# SI5324_CDR_DCXO_oscillators.net
KiCad netlist of a schematic drawn in Altium Designer
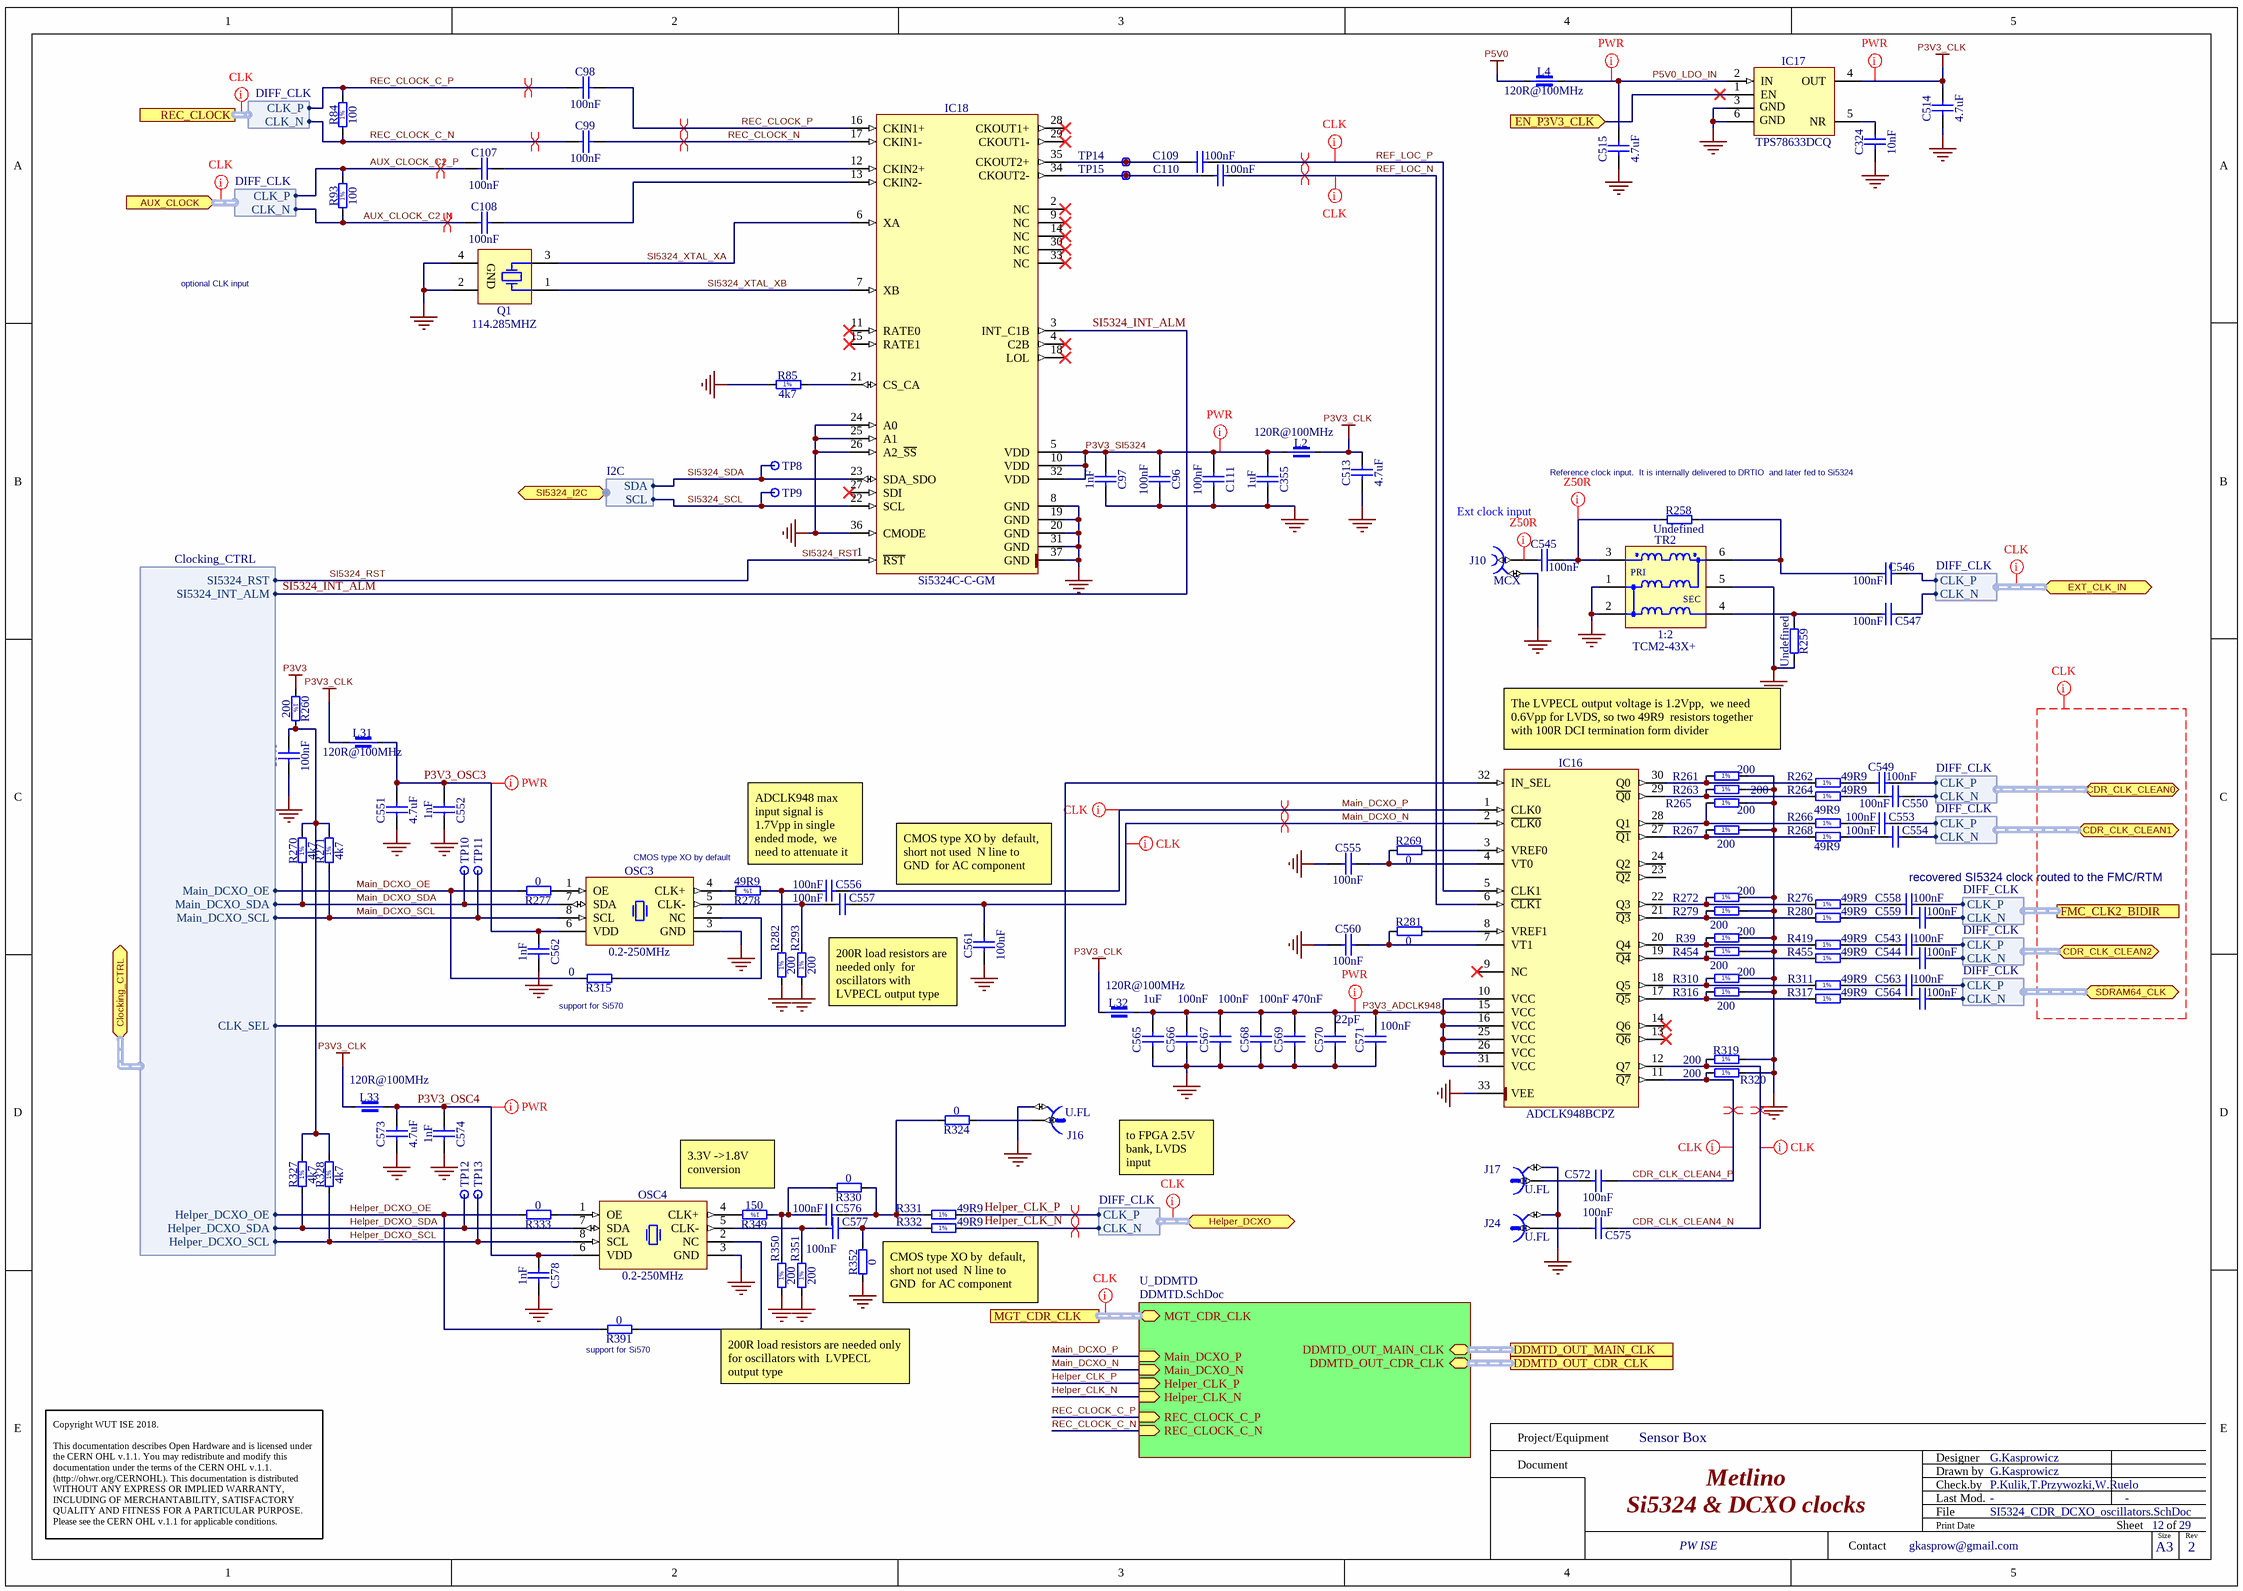
[diagram p0: SI5324_CDR_DCXO_oscillators.SchDoc]

(export (version "E")
  (design (tool "Eeschema 10.0.6"))
  (components
    (comp (ref "C96")
      (value "100nF")
      (footprint "CAPC0603X33N")
      (description "Non-polarised capacitor")
      (fields
        (field (name "MANUFACTURER PART NUMBER") "CC0201_100NF_6.3V_10%_X5R")
        (field (name "MANUFACTURER") "GENERIC")
        (field (name "AUTHOR") "CERN DEM JLC")
      )
      (libsource (lib "Capacitors") (part "Capacitor - non polarized"))
    )
    (comp (ref "C97")
      (value "1nF")
      (footprint "CAPC0603X33N")
      (description "Non-polarised capacitor")
      (fields
        (field (name "MANUFACTURER PART NUMBER") "CC0201_1NF_16V_10%_X5R")
        (field (name "MANUFACTURER") "GENERIC")
        (field (name "AUTHOR") "CERN DEM JLC")
      )
      (libsource (lib "Capacitors") (part "Capacitor - non polarized"))
    )
    (comp (ref "C98")
      (value "100nF")
      (footprint "CAPC0603X33N")
      (description "Non-polarised capacitor")
      (fields
        (field (name "MANUFACTURER PART NUMBER") "CC0201_100NF_6.3V_10%_X5R")
        (field (name "MANUFACTURER") "GENERIC")
        (field (name "AUTHOR") "CERN DEM JLC")
      )
      (libsource (lib "Capacitors") (part "Capacitor - non polarized"))
    )
    (comp (ref "C99")
      (value "100nF")
      (footprint "CAPC0603X33N")
      (description "Non-polarised capacitor")
      (fields
        (field (name "MANUFACTURER PART NUMBER") "CC0201_100NF_6.3V_10%_X5R")
        (field (name "MANUFACTURER") "GENERIC")
        (field (name "AUTHOR") "CERN DEM JLC")
      )
      (libsource (lib "Capacitors") (part "Capacitor - non polarized"))
    )
    (comp (ref "C107")
      (value "100nF")
      (footprint "CAPC0603X33N")
      (description "Non-polarised capacitor")
      (fields
        (field (name "MANUFACTURER PART NUMBER") "CC0201_100NF_6.3V_10%_X5R")
        (field (name "MANUFACTURER") "GENERIC")
        (field (name "AUTHOR") "CERN DEM JLC")
      )
      (libsource (lib "Capacitors") (part "Capacitor - non polarized"))
    )
    (comp (ref "C108")
      (value "100nF")
      (footprint "CAPC0603X33N")
      (description "Non-polarised capacitor")
      (fields
        (field (name "MANUFACTURER PART NUMBER") "CC0201_100NF_6.3V_10%_X5R")
        (field (name "MANUFACTURER") "GENERIC")
        (field (name "AUTHOR") "CERN DEM JLC")
      )
      (libsource (lib "Capacitors") (part "Capacitor - non polarized"))
    )
    (comp (ref "C109")
      (value "100nF")
      (footprint "CAPC1005X55N")
      (description "Non-polarised capacitor")
      (fields
        (field (name "MANUFACTURER PART NUMBER") "CC0402_100NF_16V_10%_X5R")
        (field (name "MANUFACTURER") "GENERIC")
        (field (name "AUTHOR") "CERN DEM JLC")
      )
      (libsource (lib "Capacitors") (part "Capacitor - non polarized"))
    )
    (comp (ref "C110")
      (value "100nF")
      (footprint "CAPC1005X55N")
      (description "Non-polarised capacitor")
      (fields
        (field (name "MANUFACTURER PART NUMBER") "CC0402_100NF_16V_10%_X5R")
        (field (name "MANUFACTURER") "GENERIC")
        (field (name "AUTHOR") "CERN DEM JLC")
      )
      (libsource (lib "Capacitors") (part "Capacitor - non polarized"))
    )
    (comp (ref "C111")
      (value "100nF")
      (footprint "CAPC0603X33N")
      (description "Non-polarised capacitor")
      (fields
        (field (name "MANUFACTURER PART NUMBER") "CC0201_100NF_6.3V_10%_X5R")
        (field (name "MANUFACTURER") "GENERIC")
        (field (name "AUTHOR") "CERN DEM JLC")
      )
      (libsource (lib "Capacitors") (part "Capacitor - non polarized"))
    )
    (comp (ref "C324")
      (value "10nF")
      (footprint "CAPC1608X87N")
      (description "Non-polarised capacitor")
      (fields
        (field (name "PART NUMBER") "CC0603_10NF_50V_5%_C0G")
        (field (name "VOLTAGE") "50V")
        (field (name "AUTHOR") "CERN DEM JLC")
      )
      (libsource (lib "Capacitors") (part "Capacitor - non polarized"))
    )
    (comp (ref "C355")
      (value "1uF")
      (footprint "CAPC1005X55N")
      (description "Non-polarised capacitor")
      (fields
        (field (name "MANUFACTURER PART NUMBER") "CC0402_1UF_16V_10%_X5R")
        (field (name "MANUFACTURER") "GENERIC")
        (field (name "AUTHOR") "CERN DEM JLC")
      )
      (libsource (lib "Capacitors") (part "Capacitor - non polarized"))
    )
    (comp (ref "C513")
      (value "4.7uF")
      (footprint "CAPC1608X90N")
      (description "Non-polarised capacitor")
      (fields
        (field (name "MANUFACTURER PART NUMBER") "CC0603_4.7UF_25V_10%_X5R")
        (field (name "MANUFACTURER") "GENERIC")
        (field (name "AUTHOR") "CERN DEM JLC")
      )
      (libsource (lib "Capacitors") (part "Capacitor - non polarized"))
    )
    (comp (ref "C514")
      (value "4.7uF")
      (footprint "CAPC1608X90N")
      (description "Non-polarised capacitor")
      (fields
        (field (name "MANUFACTURER PART NUMBER") "CC0603_4.7UF_25V_10%_X5R")
        (field (name "MANUFACTURER") "GENERIC")
        (field (name "AUTHOR") "CERN DEM JLC")
      )
      (libsource (lib "Capacitors") (part "Capacitor - non polarized"))
    )
    (comp (ref "C515")
      (value "4.7uF")
      (footprint "CAPC1608X90N")
      (description "Non-polarised capacitor")
      (fields
        (field (name "MANUFACTURER PART NUMBER") "CC0603_4.7UF_25V_10%_X5R")
        (field (name "MANUFACTURER") "GENERIC")
        (field (name "AUTHOR") "CERN DEM JLC")
      )
      (libsource (lib "Capacitors") (part "Capacitor - non polarized"))
    )
    (comp (ref "C543")
      (value "100nF")
      (footprint "CAPC0603X33N")
      (description "Non-polarised capacitor")
      (fields
        (field (name "MANUFACTURER PART NUMBER") "CC0201_100NF_6.3V_10%_X5R")
        (field (name "MANUFACTURER") "GENERIC")
        (field (name "AUTHOR") "CERN DEM JLC")
      )
      (libsource (lib "Capacitors") (part "Capacitor - non polarized"))
    )
    (comp (ref "C544")
      (value "100nF")
      (footprint "CAPC0603X33N")
      (description "Non-polarised capacitor")
      (fields
        (field (name "MANUFACTURER PART NUMBER") "CC0201_100NF_6.3V_10%_X5R")
        (field (name "MANUFACTURER") "GENERIC")
        (field (name "AUTHOR") "CERN DEM JLC")
      )
      (libsource (lib "Capacitors") (part "Capacitor - non polarized"))
    )
    (comp (ref "C545")
      (value "100nF")
      (footprint "CAPC1005X55N")
      (description "Non-polarised capacitor")
      (fields
        (field (name "MANUFACTURER PART NUMBER") "CC0402_100NF_16V_10%_X5R")
        (field (name "MANUFACTURER") "GENERIC")
        (field (name "AUTHOR") "CERN DEM JLC")
      )
      (libsource (lib "Capacitors") (part "Capacitor - non polarized"))
    )
    (comp (ref "C546")
      (value "100nF")
      (footprint "CAPC1005X55N")
      (description "Non-polarised capacitor")
      (fields
        (field (name "MANUFACTURER PART NUMBER") "CC0402_100NF_16V_10%_X5R")
        (field (name "MANUFACTURER") "GENERIC")
        (field (name "AUTHOR") "CERN DEM JLC")
      )
      (libsource (lib "Capacitors") (part "Capacitor - non polarized"))
    )
    (comp (ref "C547")
      (value "100nF")
      (footprint "CAPC1005X55N")
      (description "Non-polarised capacitor")
      (fields
        (field (name "MANUFACTURER PART NUMBER") "CC0402_100NF_16V_10%_X5R")
        (field (name "MANUFACTURER") "GENERIC")
        (field (name "AUTHOR") "CERN DEM JLC")
      )
      (libsource (lib "Capacitors") (part "Capacitor - non polarized"))
    )
    (comp (ref "C548")
      (value "100nF")
      (footprint "CAPC0603X33N")
      (description "Non-polarised capacitor")
      (fields
        (field (name "MANUFACTURER PART NUMBER") "CC0201_100NF_6.3V_10%_X5R")
        (field (name "MANUFACTURER") "GENERIC")
        (field (name "AUTHOR") "CERN DEM JLC")
      )
      (libsource (lib "Capacitors") (part "Capacitor - non polarized"))
    )
    (comp (ref "C549")
      (value "100nF")
      (footprint "CAPC0603X33N")
      (description "Non-polarised capacitor")
      (fields
        (field (name "MANUFACTURER PART NUMBER") "CC0201_100NF_6.3V_10%_X5R")
        (field (name "MANUFACTURER") "GENERIC")
        (field (name "AUTHOR") "CERN DEM JLC")
      )
      (libsource (lib "Capacitors") (part "Capacitor - non polarized"))
    )
    (comp (ref "C550")
      (value "100nF")
      (footprint "CAPC0603X33N")
      (description "Non-polarised capacitor")
      (fields
        (field (name "MANUFACTURER PART NUMBER") "CC0201_100NF_6.3V_10%_X5R")
        (field (name "MANUFACTURER") "GENERIC")
        (field (name "AUTHOR") "CERN DEM JLC")
      )
      (libsource (lib "Capacitors") (part "Capacitor - non polarized"))
    )
    (comp (ref "C551")
      (value "4.7uF")
      (footprint "CAPC1608X90N")
      (description "Non-polarised capacitor")
      (fields
        (field (name "MANUFACTURER PART NUMBER") "CC0603_4.7UF_25V_10%_X5R")
        (field (name "MANUFACTURER") "GENERIC")
        (field (name "AUTHOR") "CERN DEM JLC")
      )
      (libsource (lib "Capacitors") (part "Capacitor - non polarized"))
    )
    (comp (ref "C552")
      (value "1nF")
      (footprint "CAPC0603X33N")
      (description "Non-polarised capacitor")
      (fields
        (field (name "MANUFACTURER PART NUMBER") "CC0201_1NF_16V_10%_X5R")
        (field (name "MANUFACTURER") "GENERIC")
        (field (name "AUTHOR") "CERN DEM JLC")
      )
      (libsource (lib "Capacitors") (part "Capacitor - non polarized"))
    )
    (comp (ref "C553")
      (value "100nF")
      (footprint "CAPC0603X33N")
      (description "Non-polarised capacitor")
      (fields
        (field (name "MANUFACTURER PART NUMBER") "CC0201_100NF_6.3V_10%_X5R")
        (field (name "MANUFACTURER") "GENERIC")
        (field (name "AUTHOR") "CERN DEM JLC")
      )
      (libsource (lib "Capacitors") (part "Capacitor - non polarized"))
    )
    (comp (ref "C554")
      (value "100nF")
      (footprint "CAPC0603X33N")
      (description "Non-polarised capacitor")
      (fields
        (field (name "MANUFACTURER PART NUMBER") "CC0201_100NF_6.3V_10%_X5R")
        (field (name "MANUFACTURER") "GENERIC")
        (field (name "AUTHOR") "CERN DEM JLC")
      )
      (libsource (lib "Capacitors") (part "Capacitor - non polarized"))
    )
    (comp (ref "C555")
      (value "100nF")
      (footprint "CAPC0603X33N")
      (description "Non-polarised capacitor")
      (fields
        (field (name "MANUFACTURER PART NUMBER") "CC0201_100NF_6.3V_10%_X5R")
        (field (name "MANUFACTURER") "GENERIC")
        (field (name "AUTHOR") "CERN DEM JLC")
      )
      (libsource (lib "Capacitors") (part "Capacitor - non polarized"))
    )
    (comp (ref "C556")
      (value "100nF")
      (footprint "CAPC1005X55N")
      (description "Non-polarised capacitor")
      (fields
        (field (name "MANUFACTURER PART NUMBER") "CC0402_100NF_16V_10%_X5R")
        (field (name "MANUFACTURER") "GENERIC")
        (field (name "AUTHOR") "CERN DEM JLC")
      )
      (libsource (lib "Capacitors") (part "Capacitor - non polarized"))
    )
    (comp (ref "C557")
      (value "100nF")
      (footprint "CAPC1005X55N")
      (description "Non-polarised capacitor")
      (fields
        (field (name "MANUFACTURER PART NUMBER") "CC0402_100NF_16V_10%_X5R")
        (field (name "MANUFACTURER") "GENERIC")
        (field (name "AUTHOR") "CERN DEM JLC")
      )
      (libsource (lib "Capacitors") (part "Capacitor - non polarized"))
    )
    (comp (ref "C558")
      (value "100nF")
      (footprint "CAPC0603X33N")
      (description "Non-polarised capacitor")
      (fields
        (field (name "MANUFACTURER PART NUMBER") "CC0201_100NF_6.3V_10%_X5R")
        (field (name "MANUFACTURER") "GENERIC")
        (field (name "AUTHOR") "CERN DEM JLC")
      )
      (libsource (lib "Capacitors") (part "Capacitor - non polarized"))
    )
    (comp (ref "C559")
      (value "100nF")
      (footprint "CAPC0603X33N")
      (description "Non-polarised capacitor")
      (fields
        (field (name "MANUFACTURER PART NUMBER") "CC0201_100NF_6.3V_10%_X5R")
        (field (name "MANUFACTURER") "GENERIC")
        (field (name "AUTHOR") "CERN DEM JLC")
      )
      (libsource (lib "Capacitors") (part "Capacitor - non polarized"))
    )
    (comp (ref "C560")
      (value "100nF")
      (footprint "CAPC0603X33N")
      (description "Non-polarised capacitor")
      (fields
        (field (name "MANUFACTURER PART NUMBER") "CC0201_100NF_6.3V_10%_X5R")
        (field (name "MANUFACTURER") "GENERIC")
        (field (name "AUTHOR") "CERN DEM JLC")
      )
      (libsource (lib "Capacitors") (part "Capacitor - non polarized"))
    )
    (comp (ref "C561")
      (value "100nF")
      (footprint "CAPC0603X33N")
      (description "Non-polarised capacitor")
      (fields
        (field (name "MANUFACTURER PART NUMBER") "CC0201_100NF_6.3V_10%_X5R")
        (field (name "MANUFACTURER") "GENERIC")
        (field (name "AUTHOR") "CERN DEM JLC")
      )
      (libsource (lib "Capacitors") (part "Capacitor - non polarized"))
    )
    (comp (ref "C562")
      (value "1nF")
      (footprint "CAPC0603X33N")
      (description "Non-polarised capacitor")
      (fields
        (field (name "MANUFACTURER PART NUMBER") "CC0201_1NF_16V_10%_X5R")
        (field (name "MANUFACTURER") "GENERIC")
        (field (name "AUTHOR") "CERN DEM JLC")
      )
      (libsource (lib "Capacitors") (part "Capacitor - non polarized"))
    )
    (comp (ref "C563")
      (value "100nF")
      (footprint "CAPC0603X33N")
      (description "Non-polarised capacitor")
      (fields
        (field (name "MANUFACTURER PART NUMBER") "CC0201_100NF_6.3V_10%_X5R")
        (field (name "MANUFACTURER") "GENERIC")
        (field (name "AUTHOR") "CERN DEM JLC")
      )
      (libsource (lib "Capacitors") (part "Capacitor - non polarized"))
    )
    (comp (ref "C564")
      (value "100nF")
      (footprint "CAPC0603X33N")
      (description "Non-polarised capacitor")
      (fields
        (field (name "MANUFACTURER PART NUMBER") "CC0201_100NF_6.3V_10%_X5R")
        (field (name "MANUFACTURER") "GENERIC")
        (field (name "AUTHOR") "CERN DEM JLC")
      )
      (libsource (lib "Capacitors") (part "Capacitor - non polarized"))
    )
    (comp (ref "C565")
      (value "1uF")
      (footprint "CAPC1005X55N")
      (description "Non-polarised capacitor")
      (fields
        (field (name "MANUFACTURER PART NUMBER") "CC0402_1UF_16V_10%_X5R")
        (field (name "MANUFACTURER") "GENERIC")
        (field (name "AUTHOR") "CERN DEM JLC")
      )
      (libsource (lib "Capacitors") (part "Capacitor - non polarized"))
    )
    (comp (ref "C566")
      (value "100nF")
      (footprint "CAPC0603X33N")
      (description "Non-polarised capacitor")
      (fields
        (field (name "MANUFACTURER PART NUMBER") "CC0201_100NF_6.3V_10%_X5R")
        (field (name "MANUFACTURER") "GENERIC")
        (field (name "AUTHOR") "CERN DEM JLC")
      )
      (libsource (lib "Capacitors") (part "Capacitor - non polarized"))
    )
    (comp (ref "C567")
      (value "100nF")
      (footprint "CAPC0603X33N")
      (description "Non-polarised capacitor")
      (fields
        (field (name "MANUFACTURER PART NUMBER") "CC0201_100NF_6.3V_10%_X5R")
        (field (name "MANUFACTURER") "GENERIC")
        (field (name "AUTHOR") "CERN DEM JLC")
      )
      (libsource (lib "Capacitors") (part "Capacitor - non polarized"))
    )
    (comp (ref "C568")
      (value "100nF")
      (footprint "CAPC0603X33N")
      (description "Non-polarised capacitor")
      (fields
        (field (name "MANUFACTURER PART NUMBER") "CC0201_100NF_6.3V_10%_X5R")
        (field (name "MANUFACTURER") "GENERIC")
        (field (name "AUTHOR") "CERN DEM JLC")
      )
      (libsource (lib "Capacitors") (part "Capacitor - non polarized"))
    )
    (comp (ref "C569")
      (value "470nF")
      (footprint "CAPC1005X55N")
      (description "Non-polarised capacitor")
      (fields
        (field (name "MANUFACTURER PART NUMBER") "CC0402_470NF_16V_10%_X5R")
        (field (name "MANUFACTURER") "GENERIC")
        (field (name "AUTHOR") "CERN DEM JLC")
      )
      (libsource (lib "Capacitors") (part "Capacitor - non polarized"))
    )
    (comp (ref "C570")
      (value "22pF")
      (footprint "CAPC1005X55N")
      (description "Non-polarised capacitor")
      (fields
        (field (name "MANUFACTURER PART NUMBER") "CC0402_22PF_50V_5%_C0G")
        (field (name "MANUFACTURER") "GENERIC")
        (field (name "AUTHOR") "CERN DEM JLC")
      )
      (libsource (lib "Capacitors") (part "Capacitor - non polarized"))
    )
    (comp (ref "C571")
      (value "100nF")
      (footprint "CAPC0603X33N")
      (description "Non-polarised capacitor")
      (fields
        (field (name "MANUFACTURER PART NUMBER") "CC0201_100NF_6.3V_10%_X5R")
        (field (name "MANUFACTURER") "GENERIC")
        (field (name "AUTHOR") "CERN DEM JLC")
      )
      (libsource (lib "Capacitors") (part "Capacitor - non polarized"))
    )
    (comp (ref "C572")
      (value "100nF")
      (footprint "CAPC0603X33N")
      (description "Non-polarised capacitor")
      (fields
        (field (name "MANUFACTURER PART NUMBER") "CC0201_100NF_6.3V_10%_X5R")
        (field (name "MANUFACTURER") "GENERIC")
        (field (name "AUTHOR") "CERN DEM JLC")
      )
      (libsource (lib "Capacitors") (part "Capacitor - non polarized"))
    )
    (comp (ref "C573")
      (value "4.7uF")
      (footprint "CAPC1608X90N")
      (description "Non-polarised capacitor")
      (fields
        (field (name "MANUFACTURER PART NUMBER") "CC0603_4.7UF_25V_10%_X5R")
        (field (name "MANUFACTURER") "GENERIC")
        (field (name "AUTHOR") "CERN DEM JLC")
      )
      (libsource (lib "Capacitors") (part "Capacitor - non polarized"))
    )
    (comp (ref "C574")
      (value "1nF")
      (footprint "CAPC0603X33N")
      (description "Non-polarised capacitor")
      (fields
        (field (name "MANUFACTURER PART NUMBER") "CC0201_1NF_16V_10%_X5R")
        (field (name "MANUFACTURER") "GENERIC")
        (field (name "AUTHOR") "CERN DEM JLC")
      )
      (libsource (lib "Capacitors") (part "Capacitor - non polarized"))
    )
    (comp (ref "C575")
      (value "100nF")
      (footprint "CAPC0603X33N")
      (description "Non-polarised capacitor")
      (fields
        (field (name "MANUFACTURER PART NUMBER") "CC0201_100NF_6.3V_10%_X5R")
        (field (name "MANUFACTURER") "GENERIC")
        (field (name "AUTHOR") "CERN DEM JLC")
      )
      (libsource (lib "Capacitors") (part "Capacitor - non polarized"))
    )
    (comp (ref "C576")
      (value "100nF")
      (footprint "CAPC1005X55N")
      (description "Non-polarised capacitor")
      (fields
        (field (name "MANUFACTURER PART NUMBER") "CC0402_100NF_16V_10%_X5R")
        (field (name "MANUFACTURER") "GENERIC")
        (field (name "AUTHOR") "CERN DEM JLC")
      )
      (libsource (lib "Capacitors") (part "Capacitor - non polarized"))
    )
    (comp (ref "C577")
      (value "100nF")
      (footprint "CAPC1005X55N")
      (description "Non-polarised capacitor")
      (fields
        (field (name "MANUFACTURER PART NUMBER") "CC0402_100NF_16V_10%_X5R")
        (field (name "MANUFACTURER") "GENERIC")
        (field (name "AUTHOR") "CERN DEM JLC")
      )
      (libsource (lib "Capacitors") (part "Capacitor - non polarized"))
    )
    (comp (ref "C578")
      (value "1nF")
      (footprint "CAPC0603X33N")
      (description "Non-polarised capacitor")
      (fields
        (field (name "MANUFACTURER PART NUMBER") "CC0201_1NF_16V_10%_X5R")
        (field (name "MANUFACTURER") "GENERIC")
        (field (name "AUTHOR") "CERN DEM JLC")
      )
      (libsource (lib "Capacitors") (part "Capacitor - non polarized"))
    )
    (comp (ref "IC16")
      (value "ADCLK948BCPZ")
      (footprint "QFN50P500X500X80-33N-S285")
      (description "Two Selectable Inputs, 8 LVPECL Outputs, SiGe Clock Fanout Buffer")
      (fields (field (name "MANUFACTURER") "ANALOG DEVICES") (field (name "AUTHOR") "CERN DEM MR"))
      (libsource (lib "ICs And Semiconductors") (part "ADCLK948"))
    )
    (comp (ref "IC17")
      (value "TPS78633DCQ")
      (footprint "SOT127P700X180-6N")
      (description "Ultralow-Noise, High-PSRR, Fast, RF, 1.5A Low-Dropout Linear Regulator")
      (fields (field (name "MANUFACTURER") "TEXAS INSTRUMENTS") (field (name "AUTHOR") "CERN DEM JMW"))
      (libsource (lib "ICs And Semiconductors") (part "TPS786xxDCQ"))
    )
    (comp (ref "IC18")
      (value "Si5324C-C-GM")
      (footprint "QFN50P600X600X90-37N-S425")
      (description "Any Frequency Precision Clock Multiplier/Jitter Attenuator")
      (fields (field (name "MANUFACTURER") "SILICON LABS") (field (name "AUTHOR") "CERN DEM JLC"))
      (libsource (lib "ICs And Semiconductors") (part "Si5324"))
    )
    (comp (ref "J10")
      (value "MCX")
      (footprint "AMPHENOL_ARF2521-ND")
      (fields
        (field (name "PART NUMBER") "AMPHENOL_ARF2521-ND")
        (field (name "MANUFACTURER") "AMPHENOL")
        (field (name "AUTHOR") "GK")
      )
      (libsource (lib "LIBRARY_SCH") (part "CON_MCX"))
    )
    (comp (ref "J16")
      (value "U.FL")
      (footprint "HIROSE_U.FL-R-SMT-1(10)")
      (fields
        (field (name "MANUFACTURER PART NUMBER") "U.FL-R-SMT-1(10)")
        (field (name "MANUFACTURER") "HIROSE (HRS)")
        (field (name "PART NUMBER") "HIROSE_U.FL-R-SMT-1(10)")
        (field (name "AUTHOR") "CERN DEM JLC")
      )
      (libsource (lib "") (part "Coax_1Male_1Shield_1"))
    )
    (comp (ref "J17")
      (value "U.FL")
      (footprint "HIROSE_U.FL-R-SMT-1(10)")
      (fields
        (field (name "MANUFACTURER PART NUMBER") "U.FL-R-SMT-1(10)")
        (field (name "MANUFACTURER") "HIROSE (HRS)")
        (field (name "PART NUMBER") "HIROSE_U.FL-R-SMT-1(10)")
        (field (name "AUTHOR") "CERN DEM JLC")
      )
      (libsource (lib "Connectors") (part "Coax_1Male_1Shield"))
    )
    (comp (ref "J24")
      (value "U.FL")
      (footprint "HIROSE_U.FL-R-SMT-1(10)")
      (fields
        (field (name "MANUFACTURER PART NUMBER") "U.FL-R-SMT-1(10)")
        (field (name "MANUFACTURER") "HIROSE (HRS)")
        (field (name "PART NUMBER") "HIROSE_U.FL-R-SMT-1(10)")
        (field (name "AUTHOR") "CERN DEM JLC")
      )
      (libsource (lib "Connectors") (part "Coax_1Male_1Shield"))
    )
    (comp (ref "L2")
      (value "120R@100MHz")
      (footprint "INDC1608X95N")
      (fields
        (field (name "MANUFACTURER PART NUMBER") "BLM18PG121SN1D")
        (field (name "MANUFACTURER") "MURATA")
        (field (name "PART NUMBER") "IND0603_MURATA_BLM18PG121SN1D")
        (field (name "AUTHOR") "CERN DEM BC")
      )
      (libsource (lib "") (part "Ferrite Bead_1"))
    )
    (comp (ref "L4")
      (value "120R@100MHz")
      (footprint "INDC1608X95N")
      (fields
        (field (name "MANUFACTURER PART NUMBER") "BLM18PG121SN1D")
        (field (name "MANUFACTURER") "MURATA")
        (field (name "PART NUMBER") "IND0603_MURATA_BLM18PG121SN1D")
        (field (name "AUTHOR") "CERN DEM BC")
      )
      (libsource (lib "Inductors & Transformers") (part "Ferrite Bead"))
    )
    (comp (ref "L31")
      (value "120R@100MHz")
      (footprint "INDC1608X95N")
      (fields
        (field (name "MANUFACTURER PART NUMBER") "BLM18PG121SN1D")
        (field (name "MANUFACTURER") "MURATA")
        (field (name "PART NUMBER") "IND0603_MURATA_BLM18PG121SN1D")
        (field (name "AUTHOR") "CERN DEM BC")
      )
      (libsource (lib "Inductors & Transformers") (part "Ferrite Bead"))
    )
    (comp (ref "L32")
      (value "120R@100MHz")
      (footprint "INDC1608X95N")
      (fields
        (field (name "MANUFACTURER PART NUMBER") "BLM18PG121SN1D")
        (field (name "MANUFACTURER") "MURATA")
        (field (name "PART NUMBER") "IND0603_MURATA_BLM18PG121SN1D")
        (field (name "AUTHOR") "CERN DEM BC")
      )
      (libsource (lib "Inductors & Transformers") (part "Ferrite Bead"))
    )
    (comp (ref "L33")
      (value "120R@100MHz")
      (footprint "INDC1608X95N")
      (fields
        (field (name "MANUFACTURER PART NUMBER") "BLM18PG121SN1D")
        (field (name "MANUFACTURER") "MURATA")
        (field (name "PART NUMBER") "IND0603_MURATA_BLM18PG121SN1D")
        (field (name "AUTHOR") "CERN DEM BC")
      )
      (libsource (lib "Inductors & Transformers") (part "Ferrite Bead"))
    )
    (comp (ref "OSC3")
      (value "0.2-250MHz")
      (footprint "OSC_SILICON-LAB_SI549-A")
      (description "Any-Rate I2C Programmable XO Oscillator Si549 Series")
      (fields
        (field (name "PART NUMBER") "OSC_0.2-250MHZ_SILICON-LAB_549CBAC000112ABG")
        (field (name "MANUFACTURER") "SILICON LABS")
        (field (name "AUTHOR") "CERN DEM BC")
      )
      (libsource (lib "ICs And Semiconductors") (part "Oscillator SILICON-LAB_Si549-AB"))
    )
    (comp (ref "OSC4")
      (value "0.2-250MHz")
      (footprint "OSC_SILICON-LAB_SI549-A")
      (description "Any-Rate I2C Programmable XO Oscillator Si549 Series")
      (fields
        (field (name "PART NUMBER") "OSC_0.2-250MHZ_SILICON-LAB_549CBAC000112ABG")
        (field (name "MANUFACTURER") "SILICON LABS")
        (field (name "AUTHOR") "CERN DEM BC")
      )
      (libsource (lib "ICs And Semiconductors") (part "Oscillator SILICON-LAB_Si549-AB"))
    )
    (comp (ref "Q1")
      (value "114.285MHZ")
      (footprint "XTAL_CONNOR_CS")
      (description "Crystal 4 pins 1=XTAL Control 2=GND3=XTAL 4=GND")
      (fields
        (field (name "MANUFACTURER PART NUMBER") "CS-023-114.285M")
        (field (name "MANUFACTURER") "CONNOR-WINFIELD")
        (field (name "AUTHOR") "CERN DEM JLC")
      )
      (libsource (lib "ICs And Semiconductors") (part "Quartz Crystal 1X 2GND 3X 4GND"))
    )
    (comp (ref "R39")
      (value "200")
      (footprint "RESC1005X40N")
      (description "Resistor - 1%")
      (fields
        (field (name "MANUFACTURER PART NUMBER") "R0402_200R_1%_0.0625W_100PPM")
        (field (name "MANUFACTURER") "GENERIC")
        (field (name "AUTHOR") "CERN DEM JLC")
      )
      (libsource (lib "Resistors") (part "Resistor - 1%"))
    )
    (comp (ref "R84")
      (value "100")
      (footprint "RESC1005X40N")
      (description "Resistor - 1%")
      (fields
        (field (name "MANUFACTURER PART NUMBER") "R0402_100R_1%_0.0625W_100PPM")
        (field (name "MANUFACTURER") "GENERIC")
        (field (name "AUTHOR") "CERN DEM JLC")
      )
      (libsource (lib "Resistors") (part "Resistor - 1%"))
    )
    (comp (ref "R85")
      (value "4k7")
      (footprint "RESC1005X40N")
      (description "Resistor - 1%")
      (fields
        (field (name "MANUFACTURER PART NUMBER") "R0402_4K7_1%_0.0625W_100PPM")
        (field (name "MANUFACTURER") "GENERIC")
        (field (name "AUTHOR") "CERN DEM JLC")
      )
      (libsource (lib "Resistors") (part "Resistor - 1%"))
    )
    (comp (ref "R93")
      (value "100")
      (footprint "RESC1005X40N")
      (description "Resistor - 1%")
      (fields
        (field (name "MANUFACTURER PART NUMBER") "R0402_100R_1%_0.0625W_100PPM")
        (field (name "MANUFACTURER") "GENERIC")
        (field (name "AUTHOR") "CERN DEM JLC")
      )
      (libsource (lib "Resistors") (part "Resistor - 1%"))
    )
    (comp (ref "R258")
      (value "Undefined")
      (footprint "RESC1005X40N")
      (description "Resistor")
      (fields
        (field (name "MANUFACTURER PART NUMBER") "R0402_NO-VALUE")
        (field (name "AUTHOR") "CERN DEM JLC")
      )
      (libsource (lib "Resistors") (part "Resistor"))
    )
    (comp (ref "R259")
      (value "Undefined")
      (footprint "RESC1005X40N")
      (description "Resistor")
      (fields
        (field (name "MANUFACTURER PART NUMBER") "R0402_NO-VALUE")
        (field (name "AUTHOR") "CERN DEM JLC")
      )
      (libsource (lib "Resistors") (part "Resistor"))
    )
    (comp (ref "R260")
      (value "200")
      (footprint "RESC1005X40N")
      (description "Resistor - 1%")
      (fields
        (field (name "MANUFACTURER PART NUMBER") "R0402_200R_1%_0.0625W_100PPM")
        (field (name "MANUFACTURER") "GENERIC")
        (field (name "AUTHOR") "CERN DEM JLC")
      )
      (libsource (lib "Resistors") (part "Resistor - 1%"))
    )
    (comp (ref "R261")
      (value "200")
      (footprint "RESC1005X40N")
      (description "Resistor - 1%")
      (fields
        (field (name "MANUFACTURER PART NUMBER") "R0402_200R_1%_0.0625W_100PPM")
        (field (name "MANUFACTURER") "GENERIC")
        (field (name "AUTHOR") "CERN DEM JLC")
      )
      (libsource (lib "Resistors") (part "Resistor - 1%"))
    )
    (comp (ref "R262")
      (value "49R9")
      (footprint "RESC1005X40N")
      (description "Resistor - 1%")
      (fields
        (field (name "MANUFACTURER PART NUMBER") "R0402_49R9_1%_0.0625W_100PPM")
        (field (name "MANUFACTURER") "GENERIC")
        (field (name "AUTHOR") "CERN DEM JLC")
      )
      (libsource (lib "Resistors") (part "Resistor - 1%"))
    )
    (comp (ref "R263")
      (value "200")
      (footprint "RESC1005X40N")
      (description "Resistor - 1%")
      (fields
        (field (name "MANUFACTURER PART NUMBER") "R0402_200R_1%_0.0625W_100PPM")
        (field (name "MANUFACTURER") "GENERIC")
        (field (name "AUTHOR") "CERN DEM JLC")
      )
      (libsource (lib "Resistors") (part "Resistor - 1%"))
    )
    (comp (ref "R264")
      (value "49R9")
      (footprint "RESC1005X40N")
      (description "Resistor - 1%")
      (fields
        (field (name "MANUFACTURER PART NUMBER") "R0402_49R9_1%_0.0625W_100PPM")
        (field (name "MANUFACTURER") "GENERIC")
        (field (name "AUTHOR") "CERN DEM JLC")
      )
      (libsource (lib "Resistors") (part "Resistor - 1%"))
    )
    (comp (ref "R265")
      (value "200")
      (footprint "RESC1005X40N")
      (description "Resistor - 1%")
      (fields
        (field (name "MANUFACTURER PART NUMBER") "R0402_200R_1%_0.0625W_100PPM")
        (field (name "MANUFACTURER") "GENERIC")
        (field (name "AUTHOR") "CERN DEM JLC")
      )
      (libsource (lib "Resistors") (part "Resistor - 1%"))
    )
    (comp (ref "R266")
      (value "49R9")
      (footprint "RESC1005X40N")
      (description "Resistor - 1%")
      (fields
        (field (name "MANUFACTURER PART NUMBER") "R0402_49R9_1%_0.0625W_100PPM")
        (field (name "MANUFACTURER") "GENERIC")
        (field (name "AUTHOR") "CERN DEM JLC")
      )
      (libsource (lib "Resistors") (part "Resistor - 1%"))
    )
    (comp (ref "R267")
      (value "200")
      (footprint "RESC1005X40N")
      (description "Resistor - 1%")
      (fields
        (field (name "MANUFACTURER PART NUMBER") "R0402_200R_1%_0.0625W_100PPM")
        (field (name "MANUFACTURER") "GENERIC")
        (field (name "AUTHOR") "CERN DEM JLC")
      )
      (libsource (lib "Resistors") (part "Resistor - 1%"))
    )
    (comp (ref "R268")
      (value "49R9")
      (footprint "RESC1005X40N")
      (description "Resistor - 1%")
      (fields
        (field (name "MANUFACTURER PART NUMBER") "R0402_49R9_1%_0.0625W_100PPM")
        (field (name "MANUFACTURER") "GENERIC")
        (field (name "AUTHOR") "CERN DEM JLC")
      )
      (libsource (lib "Resistors") (part "Resistor - 1%"))
    )
    (comp (ref "R269")
      (value "0")
      (footprint "RESC1005X40N")
      (description "Resistor")
      (fields
        (field (name "MANUFACTURER PART NUMBER") "R0402_0R_JUMPER")
        (field (name "MANUFACTURER") "GENERIC")
        (field (name "AUTHOR") "CERN DEM JLC")
      )
      (libsource (lib "Resistors") (part "Resistor"))
    )
    (comp (ref "R270")
      (value "4k7")
      (footprint "RESC1005X40N")
      (description "Resistor - 1%")
      (fields
        (field (name "MANUFACTURER PART NUMBER") "R0402_4K7_1%_0.0625W_100PPM")
        (field (name "MANUFACTURER") "GENERIC")
        (field (name "AUTHOR") "CERN DEM JLC")
      )
      (libsource (lib "Resistors") (part "Resistor - 1%"))
    )
    (comp (ref "R271")
      (value "4k7")
      (footprint "RESC1005X40N")
      (description "Resistor - 1%")
      (fields
        (field (name "MANUFACTURER PART NUMBER") "R0402_4K7_1%_0.0625W_100PPM")
        (field (name "MANUFACTURER") "GENERIC")
        (field (name "AUTHOR") "CERN DEM JLC")
      )
      (libsource (lib "Resistors") (part "Resistor - 1%"))
    )
    (comp (ref "R272")
      (value "200")
      (footprint "RESC1005X40N")
      (description "Resistor - 1%")
      (fields
        (field (name "MANUFACTURER PART NUMBER") "R0402_200R_1%_0.0625W_100PPM")
        (field (name "MANUFACTURER") "GENERIC")
        (field (name "AUTHOR") "CERN DEM JLC")
      )
      (libsource (lib "Resistors") (part "Resistor - 1%"))
    )
    (comp (ref "R276")
      (value "49R9")
      (footprint "RESC1005X40N")
      (description "Resistor - 1%")
      (fields
        (field (name "MANUFACTURER PART NUMBER") "R0402_49R9_1%_0.0625W_100PPM")
        (field (name "MANUFACTURER") "GENERIC")
        (field (name "AUTHOR") "CERN DEM JLC")
      )
      (libsource (lib "Resistors") (part "Resistor - 1%"))
    )
    (comp (ref "R277")
      (value "0")
      (footprint "RESC1005X40N")
      (description "Resistor")
      (fields
        (field (name "MANUFACTURER PART NUMBER") "R0402_0R_JUMPER")
        (field (name "MANUFACTURER") "GENERIC")
        (field (name "AUTHOR") "CERN DEM JLC")
      )
      (libsource (lib "Resistors") (part "Resistor"))
    )
    (comp (ref "R278")
      (value "49R9")
      (footprint "RESC1005X40N")
      (description "Resistor - 1%")
      (fields
        (field (name "MANUFACTURER PART NUMBER") "R0402_49R9_1%_0.0625W_100PPM")
        (field (name "MANUFACTURER") "GENERIC")
        (field (name "AUTHOR") "CERN DEM JLC")
      )
      (libsource (lib "Resistors") (part "Resistor - 1%"))
    )
    (comp (ref "R279")
      (value "200")
      (footprint "RESC1005X40N")
      (description "Resistor - 1%")
      (fields
        (field (name "MANUFACTURER PART NUMBER") "R0402_200R_1%_0.0625W_100PPM")
        (field (name "MANUFACTURER") "GENERIC")
        (field (name "AUTHOR") "CERN DEM JLC")
      )
      (libsource (lib "Resistors") (part "Resistor - 1%"))
    )
    (comp (ref "R280")
      (value "49R9")
      (footprint "RESC1005X40N")
      (description "Resistor - 1%")
      (fields
        (field (name "MANUFACTURER PART NUMBER") "R0402_49R9_1%_0.0625W_100PPM")
        (field (name "MANUFACTURER") "GENERIC")
        (field (name "AUTHOR") "CERN DEM JLC")
      )
      (libsource (lib "Resistors") (part "Resistor - 1%"))
    )
    (comp (ref "R281")
      (value "0")
      (footprint "RESC1005X40N")
      (description "Resistor")
      (fields
        (field (name "MANUFACTURER PART NUMBER") "R0402_0R_JUMPER")
        (field (name "MANUFACTURER") "GENERIC")
        (field (name "AUTHOR") "CERN DEM JLC")
      )
      (libsource (lib "Resistors") (part "Resistor"))
    )
    (comp (ref "R282")
      (value "200")
      (footprint "RESC1005X40N")
      (description "Resistor - 1%")
      (fields
        (field (name "MANUFACTURER PART NUMBER") "R0402_200R_1%_0.0625W_100PPM")
        (field (name "MANUFACTURER") "GENERIC")
        (field (name "AUTHOR") "CERN DEM JLC")
      )
      (libsource (lib "Resistors") (part "Resistor - 1%"))
    )
    (comp (ref "R293")
      (value "200")
      (footprint "RESC1005X40N")
      (description "Resistor - 1%")
      (fields
        (field (name "MANUFACTURER PART NUMBER") "R0402_200R_1%_0.0625W_100PPM")
        (field (name "MANUFACTURER") "GENERIC")
        (field (name "AUTHOR") "CERN DEM JLC")
      )
      (libsource (lib "Resistors") (part "Resistor - 1%"))
    )
    (comp (ref "R310")
      (value "200")
      (footprint "RESC1005X40N")
      (description "Resistor - 1%")
      (fields
        (field (name "MANUFACTURER PART NUMBER") "R0402_200R_1%_0.0625W_100PPM")
        (field (name "MANUFACTURER") "GENERIC")
        (field (name "AUTHOR") "CERN DEM JLC")
      )
      (libsource (lib "Resistors") (part "Resistor - 1%"))
    )
    (comp (ref "R311")
      (value "49R9")
      (footprint "RESC1005X40N")
      (description "Resistor - 1%")
      (fields
        (field (name "MANUFACTURER PART NUMBER") "R0402_49R9_1%_0.0625W_100PPM")
        (field (name "MANUFACTURER") "GENERIC")
        (field (name "AUTHOR") "CERN DEM JLC")
      )
      (libsource (lib "Resistors") (part "Resistor - 1%"))
    )
    (comp (ref "R315")
      (value "0")
      (footprint "RESC1005X40N")
      (description "Resistor")
      (fields
        (field (name "MANUFACTURER PART NUMBER") "R0402_0R_JUMPER")
        (field (name "MANUFACTURER") "GENERIC")
        (field (name "AUTHOR") "CERN DEM JLC")
      )
      (libsource (lib "Resistors") (part "Resistor"))
    )
    (comp (ref "R316")
      (value "200")
      (footprint "RESC1005X40N")
      (description "Resistor - 1%")
      (fields
        (field (name "MANUFACTURER PART NUMBER") "R0402_200R_1%_0.0625W_100PPM")
        (field (name "MANUFACTURER") "GENERIC")
        (field (name "AUTHOR") "CERN DEM JLC")
      )
      (libsource (lib "Resistors") (part "Resistor - 1%"))
    )
    (comp (ref "R317")
      (value "49R9")
      (footprint "RESC1005X40N")
      (description "Resistor - 1%")
      (fields
        (field (name "MANUFACTURER PART NUMBER") "R0402_49R9_1%_0.0625W_100PPM")
        (field (name "MANUFACTURER") "GENERIC")
        (field (name "AUTHOR") "CERN DEM JLC")
      )
      (libsource (lib "Resistors") (part "Resistor - 1%"))
    )
    (comp (ref "R319")
      (value "200")
      (footprint "RESC1005X40N")
      (description "Resistor - 1%")
      (fields
        (field (name "MANUFACTURER PART NUMBER") "R0402_200R_1%_0.0625W_100PPM")
        (field (name "MANUFACTURER") "GENERIC")
        (field (name "AUTHOR") "CERN DEM JLC")
      )
      (libsource (lib "Resistors") (part "Resistor - 1%"))
    )
    (comp (ref "R320")
      (value "200")
      (footprint "RESC1005X40N")
      (description "Resistor - 1%")
      (fields
        (field (name "MANUFACTURER PART NUMBER") "R0402_200R_1%_0.0625W_100PPM")
        (field (name "MANUFACTURER") "GENERIC")
        (field (name "AUTHOR") "CERN DEM JLC")
      )
      (libsource (lib "Resistors") (part "Resistor - 1%"))
    )
    (comp (ref "R324")
      (value "0")
      (footprint "RESC1005X40N")
      (description "Resistor")
      (fields
        (field (name "MANUFACTURER PART NUMBER") "R0402_0R_JUMPER")
        (field (name "MANUFACTURER") "GENERIC")
        (field (name "AUTHOR") "CERN DEM JLC")
      )
      (libsource (lib "Resistors") (part "Resistor"))
    )
    (comp (ref "R327")
      (value "4k7")
      (footprint "RESC1005X40N")
      (description "Resistor - 1%")
      (fields
        (field (name "MANUFACTURER PART NUMBER") "R0402_4K7_1%_0.0625W_100PPM")
        (field (name "MANUFACTURER") "GENERIC")
        (field (name "AUTHOR") "CERN DEM JLC")
      )
      (libsource (lib "Resistors") (part "Resistor - 1%"))
    )
    (comp (ref "R328")
      (value "4k7")
      (footprint "RESC1005X40N")
      (description "Resistor - 1%")
      (fields
        (field (name "MANUFACTURER PART NUMBER") "R0402_4K7_1%_0.0625W_100PPM")
        (field (name "MANUFACTURER") "GENERIC")
        (field (name "AUTHOR") "CERN DEM JLC")
      )
      (libsource (lib "Resistors") (part "Resistor - 1%"))
    )
    (comp (ref "R330")
      (value "0")
      (footprint "RESC1005X40N")
      (description "Resistor")
      (fields
        (field (name "MANUFACTURER PART NUMBER") "R0402_0R_JUMPER")
        (field (name "MANUFACTURER") "GENERIC")
        (field (name "AUTHOR") "CERN DEM JLC")
      )
      (libsource (lib "Resistors") (part "Resistor"))
    )
    (comp (ref "R331")
      (value "49R9")
      (footprint "RESC1005X40N")
      (description "Resistor - 1%")
      (fields
        (field (name "MANUFACTURER PART NUMBER") "R0402_49R9_1%_0.0625W_100PPM")
        (field (name "MANUFACTURER") "GENERIC")
        (field (name "AUTHOR") "CERN DEM JLC")
      )
      (libsource (lib "Resistors") (part "Resistor - 1%"))
    )
    (comp (ref "R332")
      (value "49R9")
      (footprint "RESC1005X40N")
      (description "Resistor - 1%")
      (fields
        (field (name "MANUFACTURER PART NUMBER") "R0402_49R9_1%_0.0625W_100PPM")
        (field (name "MANUFACTURER") "GENERIC")
        (field (name "AUTHOR") "CERN DEM JLC")
      )
      (libsource (lib "Resistors") (part "Resistor - 1%"))
    )
    (comp (ref "R333")
      (value "0")
      (footprint "RESC1005X40N")
      (description "Resistor")
      (fields
        (field (name "MANUFACTURER PART NUMBER") "R0402_0R_JUMPER")
        (field (name "MANUFACTURER") "GENERIC")
        (field (name "AUTHOR") "CERN DEM JLC")
      )
      (libsource (lib "Resistors") (part "Resistor"))
    )
    (comp (ref "R349")
      (value "150")
      (footprint "RESC1005X40N")
      (description "Resistor - 1%")
      (fields
        (field (name "MANUFACTURER PART NUMBER") "R0402_150R_1%_0.0625W_100PPM")
        (field (name "MANUFACTURER") "GENERIC")
        (field (name "AUTHOR") "CERN DEM JLC")
      )
      (libsource (lib "Resistors") (part "Resistor - 1%"))
    )
    (comp (ref "R350")
      (value "200")
      (footprint "RESC1005X40N")
      (description "Resistor - 1%")
      (fields
        (field (name "MANUFACTURER PART NUMBER") "R0402_200R_1%_0.0625W_100PPM")
        (field (name "MANUFACTURER") "GENERIC")
        (field (name "AUTHOR") "CERN DEM JLC")
      )
      (libsource (lib "Resistors") (part "Resistor - 1%"))
    )
    (comp (ref "R351")
      (value "200")
      (footprint "RESC1005X40N")
      (description "Resistor - 1%")
      (fields
        (field (name "MANUFACTURER PART NUMBER") "R0402_200R_1%_0.0625W_100PPM")
        (field (name "MANUFACTURER") "GENERIC")
        (field (name "AUTHOR") "CERN DEM JLC")
      )
      (libsource (lib "Resistors") (part "Resistor - 1%"))
    )
    (comp (ref "R352")
      (value "0")
      (footprint "RESC1005X40N")
      (description "Resistor")
      (fields
        (field (name "MANUFACTURER PART NUMBER") "R0402_0R_JUMPER")
        (field (name "MANUFACTURER") "GENERIC")
        (field (name "AUTHOR") "CERN DEM JLC")
      )
      (libsource (lib "Resistors") (part "Resistor"))
    )
    (comp (ref "R391")
      (value "0")
      (footprint "RESC1005X40N")
      (description "Resistor")
      (fields
        (field (name "MANUFACTURER PART NUMBER") "R0402_0R_JUMPER")
        (field (name "MANUFACTURER") "GENERIC")
        (field (name "AUTHOR") "CERN DEM JLC")
      )
      (libsource (lib "Resistors") (part "Resistor"))
    )
    (comp (ref "R419")
      (value "49R9")
      (footprint "RESC1005X40N")
      (description "Resistor - 1%")
      (fields
        (field (name "MANUFACTURER PART NUMBER") "R0402_49R9_1%_0.0625W_100PPM")
        (field (name "MANUFACTURER") "GENERIC")
        (field (name "AUTHOR") "CERN DEM JLC")
      )
      (libsource (lib "Resistors") (part "Resistor - 1%"))
    )
    (comp (ref "R454")
      (value "200")
      (footprint "RESC1005X40N")
      (description "Resistor - 1%")
      (fields
        (field (name "MANUFACTURER PART NUMBER") "R0402_200R_1%_0.0625W_100PPM")
        (field (name "MANUFACTURER") "GENERIC")
        (field (name "AUTHOR") "CERN DEM JLC")
      )
      (libsource (lib "Resistors") (part "Resistor - 1%"))
    )
    (comp (ref "R455")
      (value "49R9")
      (footprint "RESC1005X40N")
      (description "Resistor - 1%")
      (fields
        (field (name "MANUFACTURER PART NUMBER") "R0402_49R9_1%_0.0625W_100PPM")
        (field (name "MANUFACTURER") "GENERIC")
        (field (name "AUTHOR") "CERN DEM JLC")
      )
      (libsource (lib "Resistors") (part "Resistor - 1%"))
    )
    (comp (ref "TP8")
      (value "Test Point")
      (footprint "TPS127")
      (fields (field (name "PART NUMBER") "SMD_PAD_1.27X1.27MM") (field (name "AUTHOR") "CERN DEM JLC"))
      (libsource (lib "Eletro-mechanical") (part "Test Point"))
    )
    (comp (ref "TP9")
      (value "Test Point")
      (footprint "TPS127")
      (fields (field (name "PART NUMBER") "SMD_PAD_1.27X1.27MM") (field (name "AUTHOR") "CERN DEM JLC"))
      (libsource (lib "Eletro-mechanical") (part "Test Point"))
    )
    (comp (ref "TP10")
      (value "Test Point")
      (footprint "TPS127")
      (fields (field (name "PART NUMBER") "SMD_PAD_1.27X1.27MM") (field (name "AUTHOR") "CERN DEM JLC"))
      (libsource (lib "Eletro-mechanical") (part "Test Point"))
    )
    (comp (ref "TP11")
      (value "Test Point")
      (footprint "TPS127")
      (fields (field (name "PART NUMBER") "SMD_PAD_1.27X1.27MM") (field (name "AUTHOR") "CERN DEM JLC"))
      (libsource (lib "Eletro-mechanical") (part "Test Point"))
    )
    (comp (ref "TP12")
      (value "Test Point")
      (footprint "TPS127")
      (fields (field (name "PART NUMBER") "SMD_PAD_1.27X1.27MM") (field (name "AUTHOR") "CERN DEM JLC"))
      (libsource (lib "Eletro-mechanical") (part "Test Point"))
    )
    (comp (ref "TP13")
      (value "Test Point")
      (footprint "TPS127")
      (fields (field (name "PART NUMBER") "SMD_PAD_1.27X1.27MM") (field (name "AUTHOR") "CERN DEM JLC"))
      (libsource (lib "Eletro-mechanical") (part "Test Point"))
    )
    (comp (ref "TP14")
      (value "Test Point")
      (footprint "TPS127")
      (fields (field (name "PART NUMBER") "SMD_PAD_1.27X1.27MM") (field (name "AUTHOR") "CERN DEM JLC"))
      (libsource (lib "Eletro-mechanical") (part "Test Point"))
    )
    (comp (ref "TP15")
      (value "Test Point")
      (footprint "TPS127")
      (fields (field (name "PART NUMBER") "SMD_PAD_1.27X1.27MM") (field (name "AUTHOR") "CERN DEM JLC"))
      (libsource (lib "Eletro-mechanical") (part "Test Point"))
    )
    (comp (ref "TR2")
      (value "1:2")
      (footprint "XFMR_MINI-CIRCUITS_DB1627")
      (description "50 OHMS 10 to 4000 MHz RF Transformer")
      (fields
        (field (name "PART NUMBER") "XFMR_MINI-CIRCUITS_TCM2-43X+")
        (field (name "POWER") "0.4W")
        (field (name "MANUFACTURER PART NUMBER") "TCM2-43X+")
        (field (name "AUTHOR") "CERN DEM BC")
      )
      (libsource (lib "Inductors & Transformers") (part "XFMR_MINI-CIRCUITS_TCM2-43X"))
    )
  )
  (nets
    (net (code "7") (name "/AUX_CLOCK_C2_N") (class "Default")
      (node (ref "C108") (pin "2") (pinfunction "2_2") (pintype "passive"))
      (node (ref "R93") (pin "1") (pinfunction "1_1") (pintype "passive"))
    )
    (net (code "8") (name "/AUX_CLOCK_C2_P") (class "Default")
      (node (ref "C107") (pin "2") (pinfunction "2_2") (pintype "passive"))
      (node (ref "R93") (pin "2") (pinfunction "2_2") (pintype "passive"))
    )
    (net (code "9") (name "/CDR_CLK_CLEAN4_N") (class "Default")
      (node (ref "C575") (pin "1") (pinfunction "1_1") (pintype "passive"))
      (node (ref "IC16") (pin "12") (pinfunction "Q7_12") (pintype "output"))
      (node (ref "R319") (pin "1") (pinfunction "1_1") (pintype "passive"))
    )
    (net (code "10") (name "/CDR_CLK_CLEAN4_P") (class "Default")
      (node (ref "C572") (pin "2") (pinfunction "2_2") (pintype "passive"))
      (node (ref "IC16") (pin "11") (pinfunction "~{Q7}_11") (pintype "output"))
      (node (ref "R320") (pin "1") (pinfunction "1_1") (pintype "passive"))
    )
    (net (code "11") (name "/CLK_SEL") (class "Default")
      (node (ref "IC16") (pin "32") (pinfunction "IN_SEL_32") (pintype "input"))
    )
    (net (code "14") (name "/EN_P3V3_CLK") (class "Default")
      (node (ref "IC17") (pin "1") (pinfunction "EN_1") (pintype "power_in"))
    )
    (net (code "15") (name "/Helper_CLK_N") (class "Default")
      (node (ref "R332") (pin "2") (pinfunction "2_2") (pintype "passive"))
    )
    (net (code "16") (name "/Helper_CLK_P") (class "Default")
      (node (ref "R331") (pin "2") (pinfunction "2_2") (pintype "passive"))
    )
    (net (code "17") (name "/Helper_DCXO_OE") (class "Default")
      (node (ref "R333") (pin "2") (pinfunction "2_2") (pintype "passive"))
      (node (ref "R391") (pin "2") (pinfunction "2_2") (pintype "passive"))
    )
    (net (code "18") (name "/Helper_DCXO_SCL") (class "Default")
      (node (ref "OSC4") (pin "8") (pinfunction "SCL_8") (pintype "input"))
      (node (ref "R328") (pin "1") (pinfunction "1_1") (pintype "passive"))
      (node (ref "TP13") (pin "1") (pinfunction "1_1") (pintype "bidirectional"))
    )
    (net (code "19") (name "/Helper_DCXO_SDA") (class "Default")
      (node (ref "OSC4") (pin "7") (pinfunction "SDA_7") (pintype "bidirectional"))
      (node (ref "R327") (pin "1") (pinfunction "1_1") (pintype "passive"))
      (node (ref "TP12") (pin "1") (pinfunction "1_1") (pintype "bidirectional"))
    )
    (net (code "21") (name "/Main_DCXO_N") (class "Default")
      (node (ref "C557") (pin "2") (pinfunction "2_2") (pintype "passive"))
      (node (ref "C561") (pin "2") (pinfunction "2_2") (pintype "passive"))
      (node (ref "IC16") (pin "2") (pinfunction "~{CLK0}_2") (pintype "input"))
    )
    (net (code "22") (name "/Main_DCXO_OE") (class "Default")
      (node (ref "R277") (pin "2") (pinfunction "2_2") (pintype "passive"))
      (node (ref "R315") (pin "2") (pinfunction "2_2") (pintype "passive"))
    )
    (net (code "23") (name "/Main_DCXO_P") (class "Default")
      (node (ref "C556") (pin "2") (pinfunction "2_2") (pintype "passive"))
      (node (ref "IC16") (pin "1") (pinfunction "CLK0_1") (pintype "input"))
    )
    (net (code "24") (name "/Main_DCXO_SCL") (class "Default")
      (node (ref "OSC3") (pin "8") (pinfunction "SCL_8") (pintype "input"))
      (node (ref "R271") (pin "1") (pinfunction "1_1") (pintype "passive"))
      (node (ref "TP11") (pin "1") (pinfunction "1_1") (pintype "bidirectional"))
    )
    (net (code "25") (name "/Main_DCXO_SDA") (class "Default")
      (node (ref "OSC3") (pin "7") (pinfunction "SDA_7") (pintype "bidirectional"))
      (node (ref "R270") (pin "1") (pinfunction "1_1") (pintype "passive"))
      (node (ref "TP10") (pin "1") (pinfunction "1_1") (pintype "bidirectional"))
    )
    (net (code "26") (name "/P3V3_ADCLK948") (class "Default")
      (node (ref "C565") (pin "1") (pinfunction "1_1") (pintype "passive"))
      (node (ref "C566") (pin "2") (pinfunction "2_2") (pintype "passive"))
      (node (ref "C567") (pin "2") (pinfunction "2_2") (pintype "passive"))
      (node (ref "C568") (pin "2") (pinfunction "2_2") (pintype "passive"))
      (node (ref "C569") (pin "2") (pinfunction "2_2") (pintype "passive"))
      (node (ref "C570") (pin "2") (pinfunction "2_2") (pintype "passive"))
      (node (ref "C571") (pin "2") (pinfunction "2_2") (pintype "passive"))
      (node (ref "IC16") (pin "10") (pinfunction "VCC_10") (pintype "power_in"))
      (node (ref "IC16") (pin "15") (pinfunction "VCC_15") (pintype "power_in"))
      (node (ref "IC16") (pin "16") (pinfunction "VCC_16") (pintype "power_in"))
      (node (ref "IC16") (pin "25") (pinfunction "VCC_25") (pintype "power_in"))
      (node (ref "IC16") (pin "26") (pinfunction "VCC_26") (pintype "power_in"))
      (node (ref "IC16") (pin "31") (pinfunction "VCC_31") (pintype "power_in"))
      (node (ref "L32") (pin "2") (pinfunction "2_2") (pintype "passive"))
    )
    (net (code "27") (name "/P3V3_OSC3") (class "Default")
      (node (ref "C551") (pin "2") (pinfunction "2_2") (pintype "passive"))
      (node (ref "C552") (pin "2") (pinfunction "2_2") (pintype "passive"))
      (node (ref "C562") (pin "2") (pinfunction "2_2") (pintype "passive"))
      (node (ref "L31") (pin "2") (pinfunction "2_2") (pintype "passive"))
      (node (ref "OSC3") (pin "6") (pinfunction "VDD_6") (pintype "power_in"))
    )
    (net (code "28") (name "/P3V3_OSC4") (class "Default")
      (node (ref "C573") (pin "2") (pinfunction "2_2") (pintype "passive"))
      (node (ref "C574") (pin "2") (pinfunction "2_2") (pintype "passive"))
      (node (ref "C578") (pin "2") (pinfunction "2_2") (pintype "passive"))
      (node (ref "L33") (pin "2") (pinfunction "2_2") (pintype "passive"))
      (node (ref "OSC4") (pin "6") (pinfunction "VDD_6") (pintype "power_in"))
    )
    (net (code "29") (name "/P3V3_SI5324") (class "Default")
      (node (ref "C111") (pin "2") (pinfunction "2_2") (pintype "passive"))
      (node (ref "C355") (pin "1") (pinfunction "1_1") (pintype "passive"))
      (node (ref "C96") (pin "2") (pinfunction "2_2") (pintype "passive"))
      (node (ref "C97") (pin "2") (pinfunction "2_2") (pintype "passive"))
      (node (ref "IC18") (pin "10") (pinfunction "VDD_10") (pintype "power_in"))
      (node (ref "IC18") (pin "32") (pinfunction "VDD_32") (pintype "power_in"))
      (node (ref "IC18") (pin "5") (pinfunction "VDD_5") (pintype "power_in"))
      (node (ref "L2") (pin "2") (pinfunction "2_2") (pintype "passive"))
    )
    (net (code "30") (name "/P5V0_LDO_IN") (class "Default")
      (node (ref "C515") (pin "2") (pinfunction "2_2") (pintype "passive"))
      (node (ref "IC17") (pin "2") (pinfunction "IN_2") (pintype "input"))
      (node (ref "L4") (pin "2") (pinfunction "2_2") (pintype "passive"))
    )
    (net (code "31") (name "/REC_CLOCK_C_N") (class "Default")
      (node (ref "C99") (pin "2") (pinfunction "2_2") (pintype "passive"))
      (node (ref "R84") (pin "1") (pinfunction "1_1") (pintype "passive"))
    )
    (net (code "32") (name "/REC_CLOCK_C_P") (class "Default")
      (node (ref "C98") (pin "2") (pinfunction "2_2") (pintype "passive"))
      (node (ref "R84") (pin "2") (pinfunction "2_2") (pintype "passive"))
    )
    (net (code "33") (name "/REC_CLOCK_N") (class "Default")
      (node (ref "C99") (pin "1") (pinfunction "1_1") (pintype "passive"))
      (node (ref "IC18") (pin "17") (pinfunction "CKIN1-_17") (pintype "input"))
    )
    (net (code "34") (name "/REC_CLOCK_P") (class "Default")
      (node (ref "C98") (pin "1") (pinfunction "1_1") (pintype "passive"))
      (node (ref "IC18") (pin "16") (pinfunction "CKIN1+_16") (pintype "input"))
    )
    (net (code "35") (name "/REF_LOC_N") (class "Default")
      (node (ref "C110") (pin "2") (pinfunction "2_2") (pintype "passive"))
      (node (ref "IC16") (pin "6") (pinfunction "~{CLK1}_6") (pintype "input"))
    )
    (net (code "36") (name "/REF_LOC_P") (class "Default")
      (node (ref "C109") (pin "2") (pinfunction "2_2") (pintype "passive"))
      (node (ref "IC16") (pin "5") (pinfunction "CLK1_5") (pintype "input"))
    )
    (net (code "37") (name "/SI5324_INT_ALM") (class "Default")
      (node (ref "IC18") (pin "3") (pinfunction "INT_C1B_3") (pintype "output"))
    )
    (net (code "38") (name "/SI5324_RST") (class "Default")
      (node (ref "IC18") (pin "1") (pinfunction "~{RST}_1") (pintype "input"))
    )
    (net (code "39") (name "/SI5324_SCL") (class "Default")
      (node (ref "IC18") (pin "22") (pinfunction "SCL_22") (pintype "input"))
      (node (ref "TP9") (pin "1") (pinfunction "1_1") (pintype "bidirectional"))
    )
    (net (code "40") (name "/SI5324_SDA") (class "Default")
      (node (ref "IC18") (pin "23") (pinfunction "SDA_SDO_23") (pintype "bidirectional"))
      (node (ref "TP8") (pin "1") (pinfunction "1_1") (pintype "bidirectional"))
    )
    (net (code "41") (name "/SI5324_XTAL_XA") (class "Default")
      (node (ref "IC18") (pin "6") (pinfunction "XA_6") (pintype "input"))
      (node (ref "Q1") (pin "3") (pinfunction "X_3") (pintype "passive"))
    )
    (net (code "42") (name "/SI5324_XTAL_XB") (class "Default")
      (node (ref "IC18") (pin "7") (pinfunction "XB_7") (pintype "input"))
      (node (ref "Q1") (pin "1") (pinfunction "X_1") (pintype "passive"))
    )
    (net (code "46") (name "GND") (class "Default")
      (node (ref "C111") (pin "1") (pinfunction "1_1") (pintype "passive"))
      (node (ref "C324") (pin "1") (pinfunction "1_1") (pintype "passive"))
      (node (ref "C355") (pin "2") (pinfunction "2_2") (pintype "passive"))
      (node (ref "C513") (pin "1") (pinfunction "1_1") (pintype "passive"))
      (node (ref "C514") (pin "1") (pinfunction "1_1") (pintype "passive"))
      (node (ref "C515") (pin "1") (pinfunction "1_1") (pintype "passive"))
      (node (ref "C548") (pin "1") (pinfunction "1_1") (pintype "passive"))
      (node (ref "C551") (pin "1") (pinfunction "1_1") (pintype "passive"))
      (node (ref "C552") (pin "1") (pinfunction "1_1") (pintype "passive"))
      (node (ref "C555") (pin "1") (pinfunction "1_1") (pintype "passive"))
      (node (ref "C560") (pin "1") (pinfunction "1_1") (pintype "passive"))
      (node (ref "C561") (pin "1") (pinfunction "1_1") (pintype "passive"))
      (node (ref "C562") (pin "1") (pinfunction "1_1") (pintype "passive"))
      (node (ref "C565") (pin "2") (pinfunction "2_2") (pintype "passive"))
      (node (ref "C566") (pin "1") (pinfunction "1_1") (pintype "passive"))
      (node (ref "C567") (pin "1") (pinfunction "1_1") (pintype "passive"))
      (node (ref "C568") (pin "1") (pinfunction "1_1") (pintype "passive"))
      (node (ref "C569") (pin "1") (pinfunction "1_1") (pintype "passive"))
      (node (ref "C570") (pin "1") (pinfunction "1_1") (pintype "passive"))
      (node (ref "C571") (pin "1") (pinfunction "1_1") (pintype "passive"))
      (node (ref "C573") (pin "1") (pinfunction "1_1") (pintype "passive"))
      (node (ref "C574") (pin "1") (pinfunction "1_1") (pintype "passive"))
      (node (ref "C578") (pin "1") (pinfunction "1_1") (pintype "passive"))
      (node (ref "C96") (pin "1") (pinfunction "1_1") (pintype "passive"))
      (node (ref "C97") (pin "1") (pinfunction "1_1") (pintype "passive"))
      (node (ref "IC16") (pin "33") (pinfunction "VEE_33") (pintype "power_in"))
      (node (ref "IC17") (pin "3") (pinfunction "GND_3") (pintype "power_in"))
      (node (ref "IC17") (pin "6") (pinfunction "GND_6") (pintype "power_in"))
      (node (ref "IC18") (pin "19") (pinfunction "GND_19") (pintype "power_in"))
      (node (ref "IC18") (pin "20") (pinfunction "GND_20") (pintype "power_in"))
      (node (ref "IC18") (pin "24") (pinfunction "A0_24") (pintype "input"))
      (node (ref "IC18") (pin "25") (pinfunction "A1_25") (pintype "input"))
      (node (ref "IC18") (pin "26") (pinfunction "A2_~{SS}_26") (pintype "input"))
      (node (ref "IC18") (pin "31") (pinfunction "GND_31") (pintype "power_in"))
      (node (ref "IC18") (pin "36") (pinfunction "CMODE_36") (pintype "input"))
      (node (ref "IC18") (pin "37") (pinfunction "GND_37") (pintype "power_in"))
      (node (ref "IC18") (pin "8") (pinfunction "GND_8") (pintype "power_in"))
      (node (ref "J10") (pin "2") (pinfunction "2_2") (pintype "bidirectional"))
      (node (ref "J16") (pin "2") (pinfunction "2_2") (pintype "bidirectional"))
      (node (ref "J17") (pin "2") (pinfunction "2_2") (pintype "bidirectional"))
      (node (ref "J24") (pin "2") (pinfunction "2_2") (pintype "bidirectional"))
      (node (ref "OSC3") (pin "3") (pinfunction "GND_3") (pintype "power_in"))
      (node (ref "OSC4") (pin "3") (pinfunction "GND_3") (pintype "power_in"))
      (node (ref "Q1") (pin "2") (pinfunction "GND_2") (pintype "power_in"))
      (node (ref "Q1") (pin "4") (pinfunction "GND_4") (pintype "power_in"))
      (node (ref "R259") (pin "1") (pinfunction "1_1") (pintype "passive"))
      (node (ref "R261") (pin "2") (pinfunction "2_2") (pintype "passive"))
      (node (ref "R263") (pin "2") (pinfunction "2_2") (pintype "passive"))
      (node (ref "R265") (pin "2") (pinfunction "2_2") (pintype "passive"))
      (node (ref "R267") (pin "2") (pinfunction "2_2") (pintype "passive"))
      (node (ref "R272") (pin "2") (pinfunction "2_2") (pintype "passive"))
      (node (ref "R279") (pin "2") (pinfunction "2_2") (pintype "passive"))
      (node (ref "R282") (pin "1") (pinfunction "1_1") (pintype "passive"))
      (node (ref "R293") (pin "1") (pinfunction "1_1") (pintype "passive"))
      (node (ref "R310") (pin "2") (pinfunction "2_2") (pintype "passive"))
      (node (ref "R316") (pin "2") (pinfunction "2_2") (pintype "passive"))
      (node (ref "R319") (pin "2") (pinfunction "2_2") (pintype "passive"))
      (node (ref "R320") (pin "2") (pinfunction "2_2") (pintype "passive"))
      (node (ref "R350") (pin "1") (pinfunction "1_1") (pintype "passive"))
      (node (ref "R351") (pin "1") (pinfunction "1_1") (pintype "passive"))
      (node (ref "R352") (pin "1") (pinfunction "1_1") (pintype "passive"))
      (node (ref "R39") (pin "2") (pinfunction "2_2") (pintype "passive"))
      (node (ref "R454") (pin "2") (pinfunction "2_2") (pintype "passive"))
      (node (ref "R85") (pin "1") (pinfunction "1_1") (pintype "passive"))
      (node (ref "TR2") (pin "1") (pinfunction "P1_1") (pintype "passive"))
      (node (ref "TR2") (pin "2") (pinfunction "P1_2") (pintype "passive"))
      (node (ref "TR2") (pin "5") (pinfunction "NC_5") (pintype "passive"))
    )
    (net (code "47") (name "Net-(C543-Pad1)") (class "Default")
      (node (ref "C543") (pin "1") (pinfunction "1_1") (pintype "passive"))
      (node (ref "R419") (pin "2") (pinfunction "2_2") (pintype "passive"))
    )
    (net (code "48") (name "Net-(C544-Pad1)") (class "Default")
      (node (ref "C544") (pin "1") (pinfunction "1_1") (pintype "passive"))
      (node (ref "R455") (pin "2") (pinfunction "2_2") (pintype "passive"))
    )
    (net (code "49") (name "Net-(C545-Pad1)") (class "Default")
      (node (ref "C545") (pin "1") (pinfunction "1_1") (pintype "passive"))
      (node (ref "J10") (pin "1") (pinfunction "1_1") (pintype "bidirectional"))
    )
    (net (code "50") (name "Net-(C545-Pad2)") (class "Default")
      (node (ref "C545") (pin "2") (pinfunction "2_2") (pintype "passive"))
      (node (ref "R258") (pin "2") (pinfunction "2_2") (pintype "passive"))
      (node (ref "TR2") (pin "3") (pinfunction "P1_3") (pintype "passive"))
    )
    (net (code "51") (name "Net-(C546-Pad1)") (class "Default")
      (node (ref "C546") (pin "1") (pinfunction "1_1") (pintype "passive"))
      (node (ref "R258") (pin "1") (pinfunction "1_1") (pintype "passive"))
      (node (ref "TR2") (pin "6") (pinfunction "S1_6") (pintype "passive"))
    )
    (net (code "52") (name "Net-(C547-Pad1)") (class "Default")
      (node (ref "C547") (pin "1") (pinfunction "1_1") (pintype "passive"))
      (node (ref "R259") (pin "2") (pinfunction "2_2") (pintype "passive"))
      (node (ref "TR2") (pin "4") (pinfunction "S1_4") (pintype "passive"))
    )
    (net (code "53") (name "Net-(C548-Pad2)") (class "Default")
      (node (ref "C548") (pin "2") (pinfunction "2_2") (pintype "passive"))
      (node (ref "R260") (pin "2") (pinfunction "2_2") (pintype "passive"))
      (node (ref "R270") (pin "2") (pinfunction "2_2") (pintype "passive"))
      (node (ref "R271") (pin "2") (pinfunction "2_2") (pintype "passive"))
      (node (ref "R327") (pin "2") (pinfunction "2_2") (pintype "passive"))
      (node (ref "R328") (pin "2") (pinfunction "2_2") (pintype "passive"))
    )
    (net (code "54") (name "Net-(C549-Pad1)") (class "Default")
      (node (ref "C549") (pin "1") (pinfunction "1_1") (pintype "passive"))
      (node (ref "R262") (pin "2") (pinfunction "2_2") (pintype "passive"))
    )
    (net (code "55") (name "Net-(C550-Pad1)") (class "Default")
      (node (ref "C550") (pin "1") (pinfunction "1_1") (pintype "passive"))
      (node (ref "R264") (pin "2") (pinfunction "2_2") (pintype "passive"))
    )
    (net (code "56") (name "Net-(C553-Pad1)") (class "Default")
      (node (ref "C553") (pin "1") (pinfunction "1_1") (pintype "passive"))
      (node (ref "R266") (pin "2") (pinfunction "2_2") (pintype "passive"))
    )
    (net (code "57") (name "Net-(C554-Pad1)") (class "Default")
      (node (ref "C554") (pin "1") (pinfunction "1_1") (pintype "passive"))
      (node (ref "R268") (pin "2") (pinfunction "2_2") (pintype "passive"))
    )
    (net (code "58") (name "Net-(C556-Pad1)") (class "Default")
      (node (ref "C556") (pin "1") (pinfunction "1_1") (pintype "passive"))
      (node (ref "R278") (pin "1") (pinfunction "1_1") (pintype "passive"))
      (node (ref "R282") (pin "2") (pinfunction "2_2") (pintype "passive"))
    )
    (net (code "59") (name "Net-(C558-Pad1)") (class "Default")
      (node (ref "C558") (pin "1") (pinfunction "1_1") (pintype "passive"))
      (node (ref "R276") (pin "2") (pinfunction "2_2") (pintype "passive"))
    )
    (net (code "60") (name "Net-(C559-Pad1)") (class "Default")
      (node (ref "C559") (pin "1") (pinfunction "1_1") (pintype "passive"))
      (node (ref "R280") (pin "2") (pinfunction "2_2") (pintype "passive"))
    )
    (net (code "61") (name "Net-(C563-Pad1)") (class "Default")
      (node (ref "C563") (pin "1") (pinfunction "1_1") (pintype "passive"))
      (node (ref "R311") (pin "2") (pinfunction "2_2") (pintype "passive"))
    )
    (net (code "62") (name "Net-(C564-Pad1)") (class "Default")
      (node (ref "C564") (pin "1") (pinfunction "1_1") (pintype "passive"))
      (node (ref "R317") (pin "2") (pinfunction "2_2") (pintype "passive"))
    )
    (net (code "63") (name "Net-(C572-Pad1)") (class "Default")
      (node (ref "C572") (pin "1") (pinfunction "1_1") (pintype "passive"))
      (node (ref "J17") (pin "1") (pinfunction "1_1") (pintype "bidirectional"))
    )
    (net (code "64") (name "Net-(C575-Pad2)") (class "Default")
      (node (ref "C575") (pin "2") (pinfunction "2_2") (pintype "passive"))
      (node (ref "J24") (pin "1") (pinfunction "1_1") (pintype "bidirectional"))
    )
    (net (code "65") (name "Net-(C576-Pad1)") (class "Default")
      (node (ref "C576") (pin "1") (pinfunction "1_1") (pintype "passive"))
      (node (ref "R330") (pin "2") (pinfunction "2_2") (pintype "passive"))
      (node (ref "R349") (pin "1") (pinfunction "1_1") (pintype "passive"))
      (node (ref "R350") (pin "2") (pinfunction "2_2") (pintype "passive"))
    )
    (net (code "66") (name "Net-(C576-Pad2)") (class "Default")
      (node (ref "C576") (pin "2") (pinfunction "2_2") (pintype "passive"))
      (node (ref "R324") (pin "2") (pinfunction "2_2") (pintype "passive"))
      (node (ref "R330") (pin "1") (pinfunction "1_1") (pintype "passive"))
      (node (ref "R331") (pin "1") (pinfunction "1_1") (pintype "passive"))
    )
    (net (code "67") (name "Net-(C577-Pad2)") (class "Default")
      (node (ref "C577") (pin "2") (pinfunction "2_2") (pintype "passive"))
      (node (ref "R332") (pin "1") (pinfunction "1_1") (pintype "passive"))
      (node (ref "R352") (pin "2") (pinfunction "2_2") (pintype "passive"))
    )
    (net (code "68") (name "Net-(IC16-Q0)") (class "Default")
      (node (ref "IC16") (pin "30") (pinfunction "Q0_30") (pintype "output"))
      (node (ref "R261") (pin "1") (pinfunction "1_1") (pintype "passive"))
      (node (ref "R262") (pin "1") (pinfunction "1_1") (pintype "passive"))
    )
    (net (code "69") (name "Net-(IC16-Q1)") (class "Default")
      (node (ref "IC16") (pin "28") (pinfunction "Q1_28") (pintype "output"))
      (node (ref "R265") (pin "1") (pinfunction "1_1") (pintype "passive"))
      (node (ref "R266") (pin "1") (pinfunction "1_1") (pintype "passive"))
    )
    (net (code "70") (name "Net-(IC16-Q3)") (class "Default")
      (node (ref "IC16") (pin "22") (pinfunction "Q3_22") (pintype "output"))
      (node (ref "R272") (pin "1") (pinfunction "1_1") (pintype "passive"))
      (node (ref "R276") (pin "1") (pinfunction "1_1") (pintype "passive"))
    )
    (net (code "71") (name "Net-(IC16-Q4)") (class "Default")
      (node (ref "IC16") (pin "20") (pinfunction "Q4_20") (pintype "output"))
      (node (ref "R39") (pin "1") (pinfunction "1_1") (pintype "passive"))
      (node (ref "R419") (pin "1") (pinfunction "1_1") (pintype "passive"))
    )
    (net (code "72") (name "Net-(IC16-Q5)") (class "Default")
      (node (ref "IC16") (pin "18") (pinfunction "Q5_18") (pintype "output"))
      (node (ref "R310") (pin "1") (pinfunction "1_1") (pintype "passive"))
      (node (ref "R311") (pin "1") (pinfunction "1_1") (pintype "passive"))
    )
    (net (code "73") (name "Net-(IC16-VREF0)") (class "Default")
      (node (ref "IC16") (pin "3") (pinfunction "VREF0_3") (pintype "input"))
      (node (ref "R269") (pin "2") (pinfunction "2_2") (pintype "passive"))
    )
    (net (code "74") (name "Net-(IC16-VREF1)") (class "Default")
      (node (ref "IC16") (pin "8") (pinfunction "VREF1_8") (pintype "input"))
      (node (ref "R281") (pin "2") (pinfunction "2_2") (pintype "passive"))
    )
    (net (code "75") (name "Net-(IC16-VT0)") (class "Default")
      (node (ref "C555") (pin "2") (pinfunction "2_2") (pintype "passive"))
      (node (ref "IC16") (pin "4") (pinfunction "VT0_4") (pintype "passive"))
      (node (ref "R269") (pin "1") (pinfunction "1_1") (pintype "passive"))
    )
    (net (code "76") (name "Net-(IC16-VT1)") (class "Default")
      (node (ref "C560") (pin "2") (pinfunction "2_2") (pintype "passive"))
      (node (ref "IC16") (pin "7") (pinfunction "VT1_7") (pintype "passive"))
      (node (ref "R281") (pin "1") (pinfunction "1_1") (pintype "passive"))
    )
    (net (code "77") (name "Net-(IC16-~{Q0})") (class "Default")
      (node (ref "IC16") (pin "29") (pinfunction "~{Q0}_29") (pintype "output"))
      (node (ref "R263") (pin "1") (pinfunction "1_1") (pintype "passive"))
      (node (ref "R264") (pin "1") (pinfunction "1_1") (pintype "passive"))
    )
    (net (code "78") (name "Net-(IC16-~{Q1})") (class "Default")
      (node (ref "IC16") (pin "27") (pinfunction "~{Q1}_27") (pintype "output"))
      (node (ref "R267") (pin "1") (pinfunction "1_1") (pintype "passive"))
      (node (ref "R268") (pin "1") (pinfunction "1_1") (pintype "passive"))
    )
    (net (code "79") (name "Net-(IC16-~{Q3})") (class "Default")
      (node (ref "IC16") (pin "21") (pinfunction "~{Q3}_21") (pintype "output"))
      (node (ref "R279") (pin "1") (pinfunction "1_1") (pintype "passive"))
      (node (ref "R280") (pin "1") (pinfunction "1_1") (pintype "passive"))
    )
    (net (code "80") (name "Net-(IC16-~{Q4})") (class "Default")
      (node (ref "IC16") (pin "19") (pinfunction "~{Q4}_19") (pintype "output"))
      (node (ref "R454") (pin "1") (pinfunction "1_1") (pintype "passive"))
      (node (ref "R455") (pin "1") (pinfunction "1_1") (pintype "passive"))
    )
    (net (code "81") (name "Net-(IC16-~{Q5})") (class "Default")
      (node (ref "IC16") (pin "17") (pinfunction "~{Q5}_17") (pintype "output"))
      (node (ref "R316") (pin "1") (pinfunction "1_1") (pintype "passive"))
      (node (ref "R317") (pin "1") (pinfunction "1_1") (pintype "passive"))
    )
    (net (code "82") (name "Net-(IC17-NR)") (class "Default")
      (node (ref "C324") (pin "2") (pinfunction "2_2") (pintype "passive"))
      (node (ref "IC17") (pin "5") (pinfunction "NR_5") (pintype "passive"))
    )
    (net (code "83") (name "Net-(IC18-CKIN2+)") (class "Default")
      (node (ref "C107") (pin "1") (pinfunction "1_1") (pintype "passive"))
      (node (ref "IC18") (pin "12") (pinfunction "CKIN2+_12") (pintype "input"))
    )
    (net (code "84") (name "Net-(IC18-CKIN2-)") (class "Default")
      (node (ref "C108") (pin "1") (pinfunction "1_1") (pintype "passive"))
      (node (ref "IC18") (pin "13") (pinfunction "CKIN2-_13") (pintype "input"))
    )
    (net (code "85") (name "Net-(IC18-CKOUT2+)") (class "Default")
      (node (ref "C109") (pin "1") (pinfunction "1_1") (pintype "passive"))
      (node (ref "IC18") (pin "35") (pinfunction "CKOUT2+_35") (pintype "output"))
      (node (ref "TP14") (pin "1") (pinfunction "1_1") (pintype "bidirectional"))
    )
    (net (code "86") (name "Net-(IC18-CKOUT2-)") (class "Default")
      (node (ref "C110") (pin "1") (pinfunction "1_1") (pintype "passive"))
      (node (ref "IC18") (pin "34") (pinfunction "CKOUT2-_34") (pintype "output"))
      (node (ref "TP15") (pin "1") (pinfunction "1_1") (pintype "bidirectional"))
    )
    (net (code "87") (name "Net-(IC18-CS_CA)") (class "Default")
      (node (ref "IC18") (pin "21") (pinfunction "CS_CA_21") (pintype "bidirectional"))
      (node (ref "R85") (pin "2") (pinfunction "2_2") (pintype "passive"))
    )
    (net (code "88") (name "Net-(J16-Pad1)") (class "Default")
      (node (ref "J16") (pin "1") (pinfunction "1_1") (pintype "bidirectional"))
      (node (ref "R324") (pin "1") (pinfunction "1_1") (pintype "passive"))
    )
    (net (code "89") (name "Net-(OSC3-CLK+)") (class "Default")
      (node (ref "OSC3") (pin "4") (pinfunction "CLK+_4") (pintype "output"))
      (node (ref "R278") (pin "2") (pinfunction "2_2") (pintype "passive"))
    )
    (net (code "90") (name "Net-(OSC3-CLK-)") (class "Default")
      (node (ref "C557") (pin "1") (pinfunction "1_1") (pintype "passive"))
      (node (ref "OSC3") (pin "5") (pinfunction "CLK-_5") (pintype "output"))
      (node (ref "R293") (pin "2") (pinfunction "2_2") (pintype "passive"))
    )
    (net (code "91") (name "Net-(OSC3-NC)") (class "Default")
      (node (ref "OSC3") (pin "2") (pinfunction "NC_2") (pintype "passive"))
      (node (ref "R315") (pin "1") (pinfunction "1_1") (pintype "passive"))
    )
    (net (code "92") (name "Net-(OSC3-OE)") (class "Default")
      (node (ref "OSC3") (pin "1") (pinfunction "OE_1") (pintype "input"))
      (node (ref "R277") (pin "1") (pinfunction "1_1") (pintype "passive"))
    )
    (net (code "93") (name "Net-(OSC4-CLK+)") (class "Default")
      (node (ref "OSC4") (pin "4") (pinfunction "CLK+_4") (pintype "output"))
      (node (ref "R349") (pin "2") (pinfunction "2_2") (pintype "passive"))
    )
    (net (code "94") (name "Net-(OSC4-CLK-)") (class "Default")
      (node (ref "C577") (pin "1") (pinfunction "1_1") (pintype "passive"))
      (node (ref "OSC4") (pin "5") (pinfunction "CLK-_5") (pintype "output"))
      (node (ref "R351") (pin "2") (pinfunction "2_2") (pintype "passive"))
    )
    (net (code "95") (name "Net-(OSC4-NC)") (class "Default")
      (node (ref "OSC4") (pin "2") (pinfunction "NC_2") (pintype "passive"))
      (node (ref "R391") (pin "1") (pinfunction "1_1") (pintype "passive"))
    )
    (net (code "96") (name "Net-(OSC4-OE)") (class "Default")
      (node (ref "OSC4") (pin "1") (pinfunction "OE_1") (pintype "input"))
      (node (ref "R333") (pin "1") (pinfunction "1_1") (pintype "passive"))
    )
    (net (code "97") (name "P3V3") (class "Default")
      (node (ref "R260") (pin "1") (pinfunction "1_1") (pintype "passive"))
    )
    (net (code "98") (name "P3V3_CLK") (class "Default")
      (node (ref "C513") (pin "2") (pinfunction "2_2") (pintype "passive"))
      (node (ref "C514") (pin "2") (pinfunction "2_2") (pintype "passive"))
      (node (ref "IC17") (pin "4") (pinfunction "OUT_4") (pintype "power_in"))
      (node (ref "L2") (pin "1") (pinfunction "1_1") (pintype "passive"))
      (node (ref "L31") (pin "1") (pinfunction "1_1") (pintype "passive"))
      (node (ref "L32") (pin "1") (pinfunction "1_1") (pintype "passive"))
      (node (ref "L33") (pin "1") (pinfunction "1_1") (pintype "passive"))
    )
    (net (code "99") (name "P5V0") (class "Default")
      (node (ref "L4") (pin "1") (pinfunction "1_1") (pintype "passive"))
    )
    (net (code "100") (name "unconnected-(C543-Pad2)") (class "Default")
      (node (ref "C543") (pin "2") (pinfunction "2_2") (pintype "passive"))
    )
    (net (code "101") (name "unconnected-(C544-Pad2)") (class "Default")
      (node (ref "C544") (pin "2") (pinfunction "2_2") (pintype "passive"))
    )
    (net (code "102") (name "unconnected-(C546-Pad2)") (class "Default")
      (node (ref "C546") (pin "2") (pinfunction "2_2") (pintype "passive"))
    )
    (net (code "103") (name "unconnected-(C547-Pad2)") (class "Default")
      (node (ref "C547") (pin "2") (pinfunction "2_2") (pintype "passive"))
    )
    (net (code "104") (name "unconnected-(C549-Pad2)") (class "Default")
      (node (ref "C549") (pin "2") (pinfunction "2_2") (pintype "passive"))
    )
    (net (code "105") (name "unconnected-(C550-Pad2)") (class "Default")
      (node (ref "C550") (pin "2") (pinfunction "2_2") (pintype "passive"))
    )
    (net (code "106") (name "unconnected-(C553-Pad2)") (class "Default")
      (node (ref "C553") (pin "2") (pinfunction "2_2") (pintype "passive"))
    )
    (net (code "107") (name "unconnected-(C554-Pad2)") (class "Default")
      (node (ref "C554") (pin "2") (pinfunction "2_2") (pintype "passive"))
    )
    (net (code "108") (name "unconnected-(C558-Pad2)") (class "Default")
      (node (ref "C558") (pin "2") (pinfunction "2_2") (pintype "passive"))
    )
    (net (code "109") (name "unconnected-(C559-Pad2)") (class "Default")
      (node (ref "C559") (pin "2") (pinfunction "2_2") (pintype "passive"))
    )
    (net (code "110") (name "unconnected-(C563-Pad2)") (class "Default")
      (node (ref "C563") (pin "2") (pinfunction "2_2") (pintype "passive"))
    )
    (net (code "111") (name "unconnected-(C564-Pad2)") (class "Default")
      (node (ref "C564") (pin "2") (pinfunction "2_2") (pintype "passive"))
    )
    (net (code "112") (name "unconnected-(IC16-NC-Pad9)") (class "Default")
      (node (ref "IC16") (pin "9") (pinfunction "NC_9") (pintype "passive+no_connect"))
    )
    (net (code "113") (name "unconnected-(IC16-Q2-Pad24)") (class "Default")
      (node (ref "IC16") (pin "24") (pinfunction "Q2_24") (pintype "output"))
    )
    (net (code "114") (name "unconnected-(IC16-Q6-Pad14)") (class "Default")
      (node (ref "IC16") (pin "14") (pinfunction "Q6_14") (pintype "output+no_connect"))
    )
    (net (code "115") (name "unconnected-(IC16-~{Q2}-Pad23)") (class "Default")
      (node (ref "IC16") (pin "23") (pinfunction "~{Q2}_23") (pintype "output"))
    )
    (net (code "116") (name "unconnected-(IC16-~{Q6}-Pad13)") (class "Default")
      (node (ref "IC16") (pin "13") (pinfunction "~{Q6}_13") (pintype "output+no_connect"))
    )
    (net (code "117") (name "unconnected-(IC18-C2B-Pad4)") (class "Default")
      (node (ref "IC18") (pin "4") (pinfunction "C2B_4") (pintype "output+no_connect"))
    )
    (net (code "118") (name "unconnected-(IC18-CKOUT1+-Pad28)") (class "Default")
      (node (ref "IC18") (pin "28") (pinfunction "CKOUT1+_28") (pintype "output+no_connect"))
    )
    (net (code "119") (name "unconnected-(IC18-CKOUT1--Pad29)") (class "Default")
      (node (ref "IC18") (pin "29") (pinfunction "CKOUT1-_29") (pintype "output+no_connect"))
    )
    (net (code "120") (name "unconnected-(IC18-LOL-Pad18)") (class "Default")
      (node (ref "IC18") (pin "18") (pinfunction "LOL_18") (pintype "output+no_connect"))
    )
    (net (code "121") (name "unconnected-(IC18-NC-Pad2)") (class "Default")
      (node (ref "IC18") (pin "2") (pinfunction "NC_2") (pintype "passive+no_connect"))
    )
    (net (code "122") (name "unconnected-(IC18-NC-Pad9)") (class "Default")
      (node (ref "IC18") (pin "9") (pinfunction "NC_9") (pintype "passive+no_connect"))
    )
    (net (code "123") (name "unconnected-(IC18-NC-Pad14)") (class "Default")
      (node (ref "IC18") (pin "14") (pinfunction "NC_14") (pintype "passive+no_connect"))
    )
    (net (code "124") (name "unconnected-(IC18-NC-Pad30)") (class "Default")
      (node (ref "IC18") (pin "30") (pinfunction "NC_30") (pintype "passive+no_connect"))
    )
    (net (code "125") (name "unconnected-(IC18-NC-Pad33)") (class "Default")
      (node (ref "IC18") (pin "33") (pinfunction "NC_33") (pintype "passive+no_connect"))
    )
    (net (code "126") (name "unconnected-(IC18-RATE0-Pad11)") (class "Default")
      (node (ref "IC18") (pin "11") (pinfunction "RATE0_11") (pintype "input+no_connect"))
    )
    (net (code "127") (name "unconnected-(IC18-RATE1-Pad15)") (class "Default")
      (node (ref "IC18") (pin "15") (pinfunction "RATE1_15") (pintype "input+no_connect"))
    )
    (net (code "128") (name "unconnected-(IC18-SDI-Pad27)") (class "Default")
      (node (ref "IC18") (pin "27") (pinfunction "SDI_27") (pintype "input+no_connect"))
    )
  )
)
